# SmartSocket_V1_0.net
KiCad netlist of a schematic drawn in Altium Designer
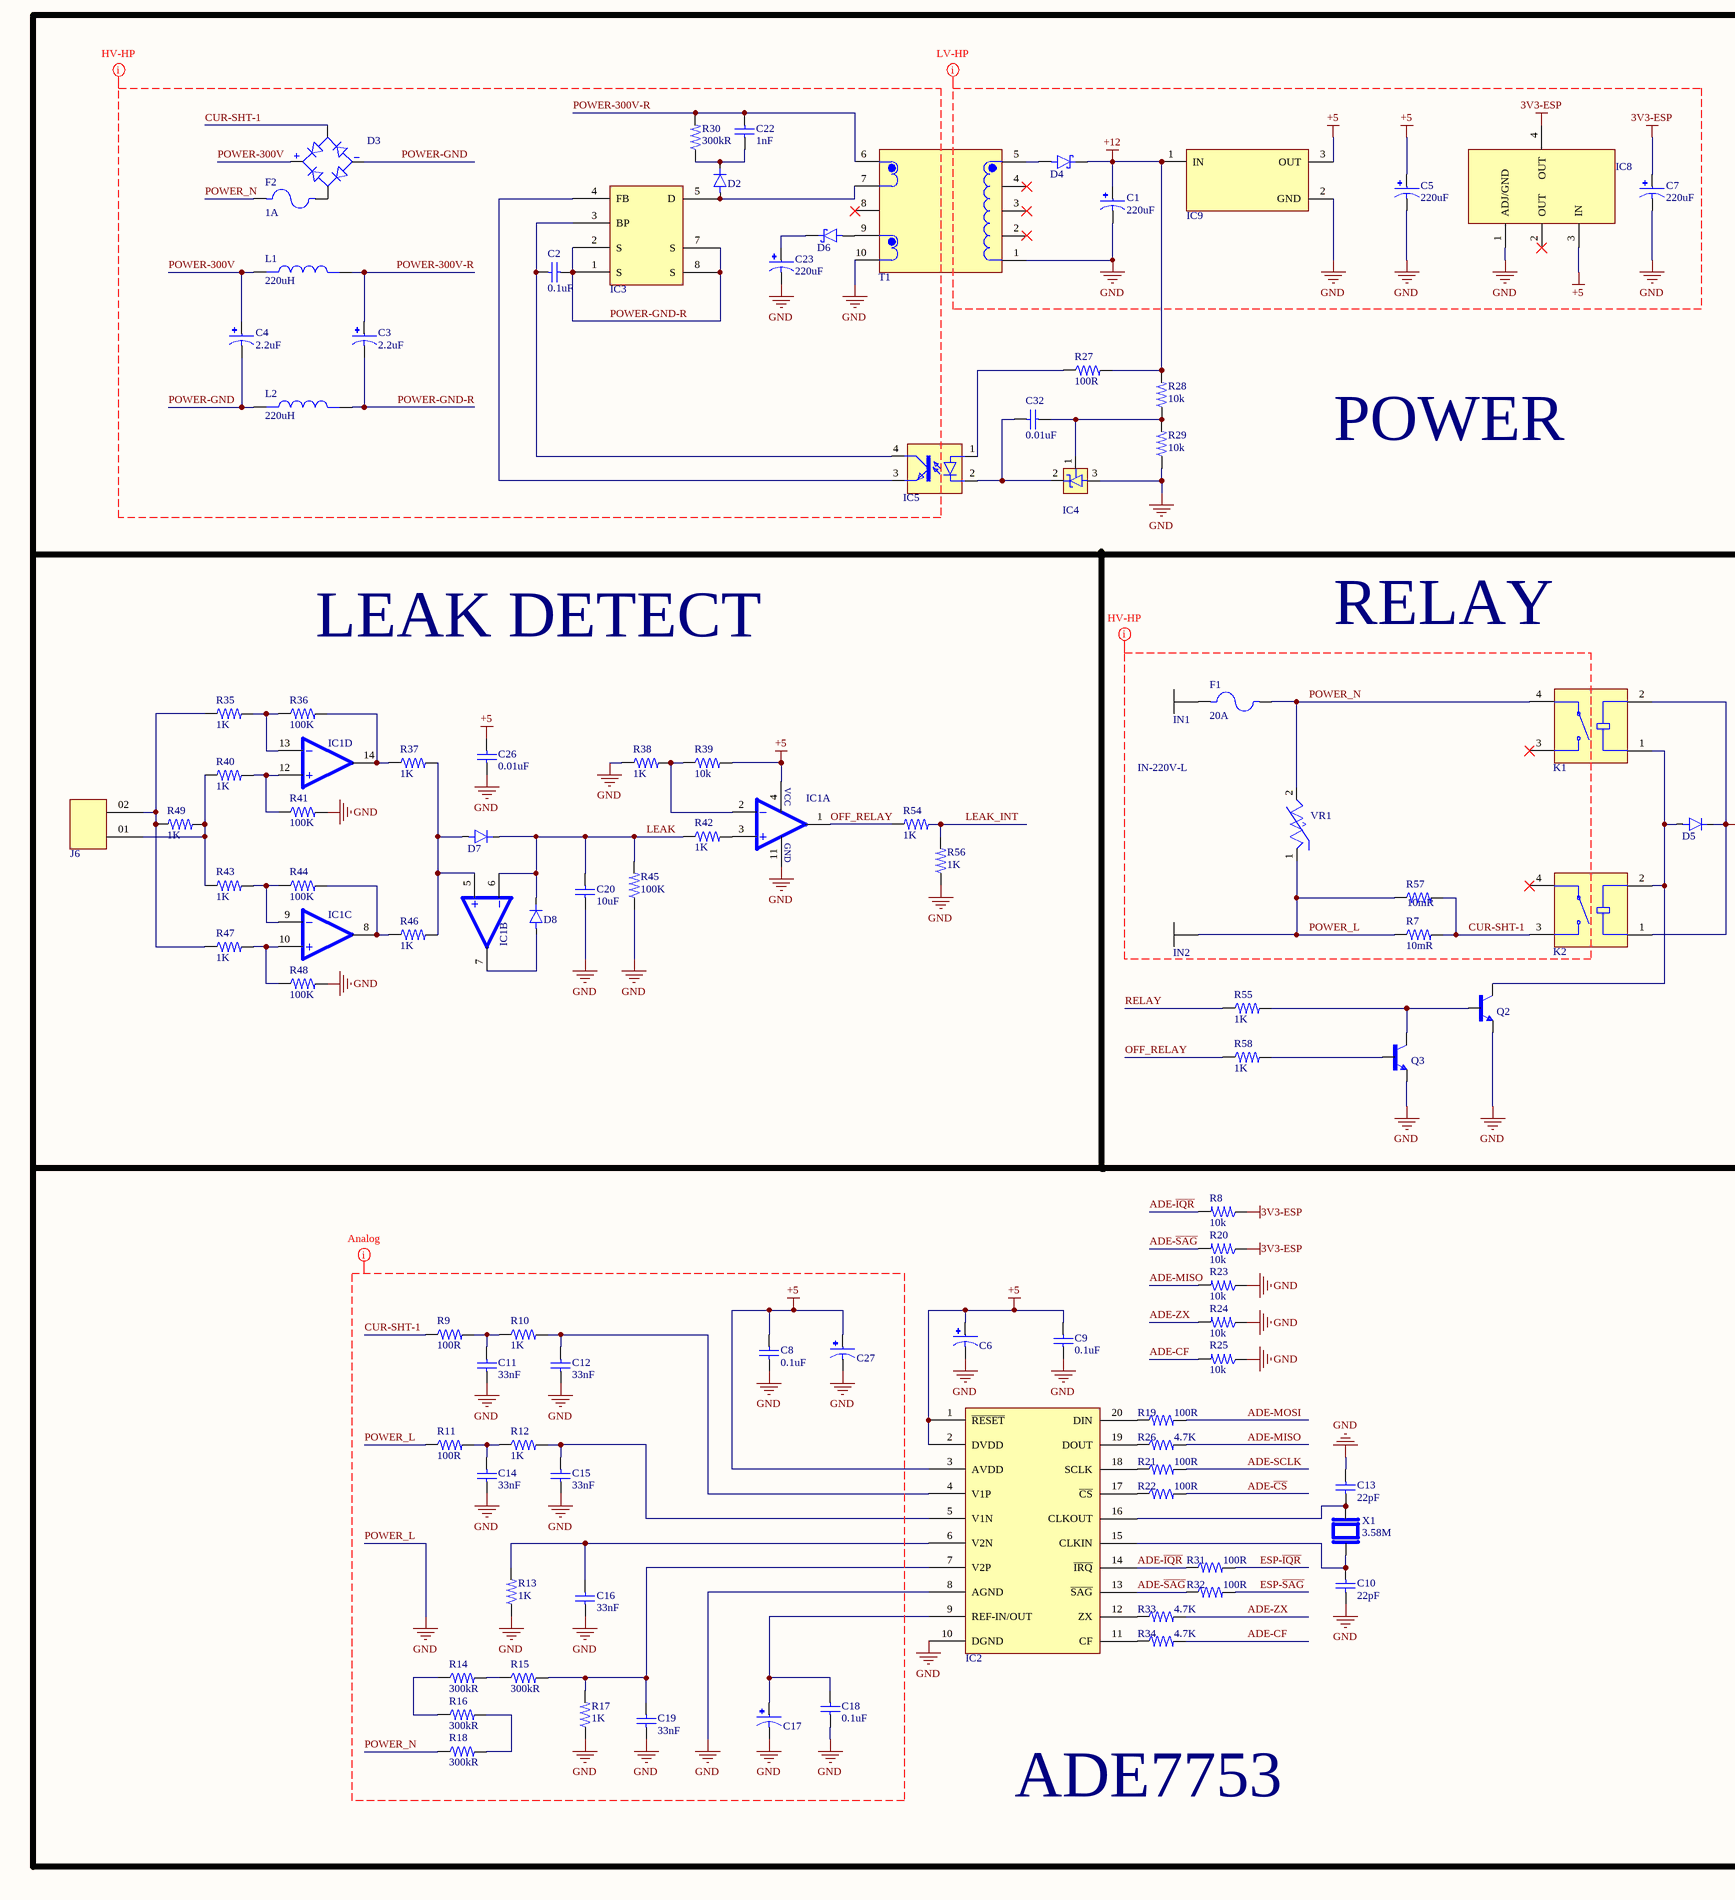
[diagram p0: SmartSocket V1.0.SchDoc, left]
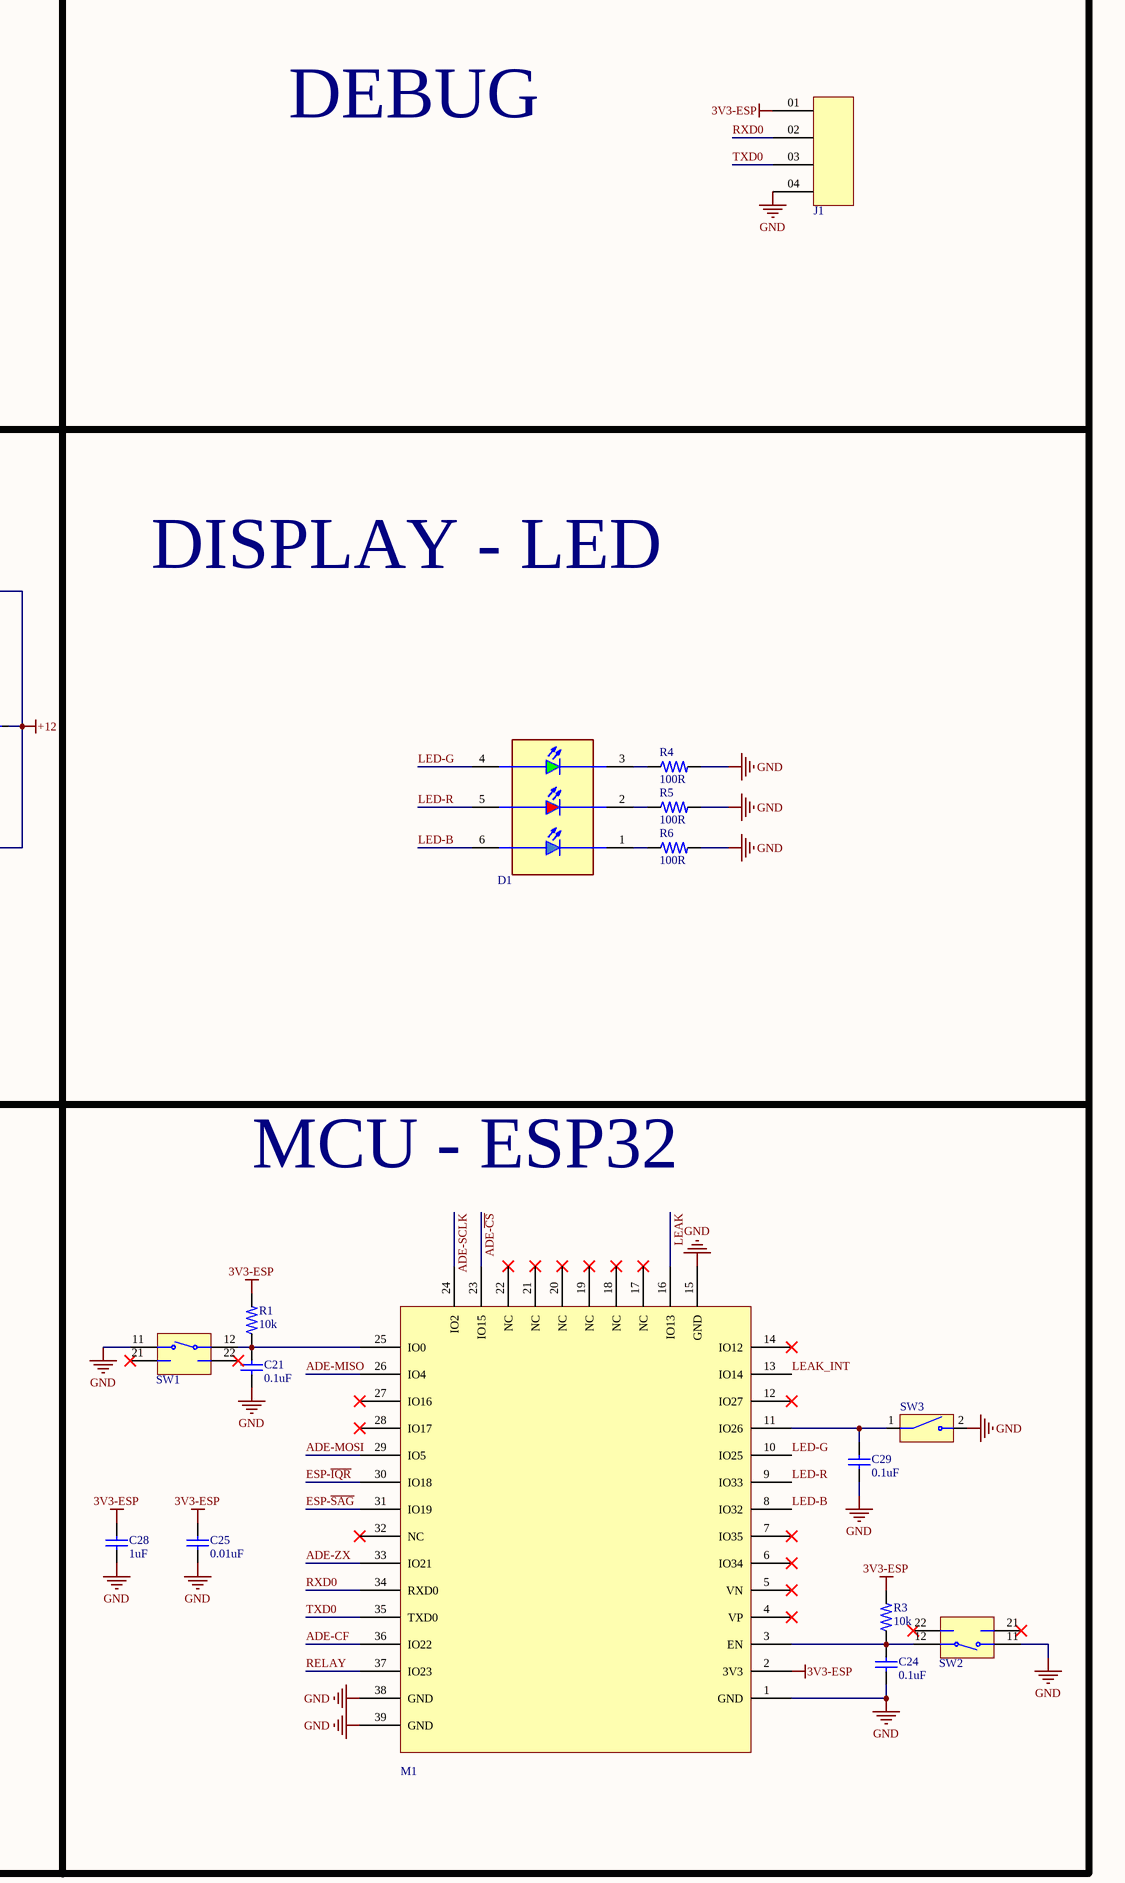
[diagram p1: SmartSocket V1.0.SchDoc, right]

(export (version "E")
  (design (tool "Eeschema 10.0.6"))
  (components
    (comp (ref "C1")
      (value "220uF")
      (footprint "SMD-DxLxW-6.3x6.6x6.6-PEC")
      (description "Cap Aluminum Polymer 220uF 16VDC 20% (6.3 X 5.9mm) SMD 0.022 Ohm 1040mA 1000h 125C T/R")
      (fields
        (field (name "MANUFACTURER") "Panasonic")
        (field (name "MANUFACTURER PART NUMBER") "16SVPK220M")
        (field (name "DESIGNER") "TVBac")
      )
      (libsource (lib "Capacitors") (part "CAP; 220uF; 16V; SMD; 16SVPK220M"))
    )
    (comp (ref "C2")
      (value "0.1uF")
      (footprint "SMD-CAP-0603-YAGEO")
      (description "Multilayer Ceramic Capacitor, 0.1 uF, 50 V, ï¿½ 5%, X7R, 0603 [1608 Metric]")
      (fields
        (field (name "MANUFACTURER") "Yageo")
        (field (name "MANUFACTURER PART NUMBER") "CC0603JRX7R9BB104")
        (field (name "DESIGNER") "TVBac")
      )
      (libsource (lib "Capacitors") (part "CAP; 0.1uF; 50V; 0603; SMD; CC0603JRX7R9BB104"))
    )
    (comp (ref "C3")
      (value "2.2uF")
      (footprint "TH-CAP-HxD-12.5x8.0-PEC")
      (description "Cap Aluminum Lytic 2.2uF 400V 20% (8 X 11.5mm) Radial 3.5mm 50mA 2000h 85C Automotive Bulk")
      (fields
        (field (name "MANUFACTURER") "Panasonic")
        (field (name "MANUFACTURER PART NUMBER") "ECA-2GM2R2")
        (field (name "DESIGNER") "TVBac")
      )
      (libsource (lib "Capacitors") (part "CAP; TH; 2.2uF; 400V; ECA-2GM2R2"))
    )
    (comp (ref "C4")
      (value "2.2uF")
      (footprint "TH-CAP-HxD-12.5x8.0-PEC")
      (description "Cap Aluminum Lytic 2.2uF 400V 20% (8 X 11.5mm) Radial 3.5mm 50mA 2000h 85C Automotive Bulk")
      (fields
        (field (name "MANUFACTURER") "Panasonic")
        (field (name "MANUFACTURER PART NUMBER") "ECA-2GM2R2")
        (field (name "DESIGNER") "TVBac")
      )
      (libsource (lib "Capacitors") (part "CAP; TH; 2.2uF; 400V; ECA-2GM2R2"))
    )
    (comp (ref "C5")
      (value "220uF")
      (footprint "SMD-DxLxW-6.3x6.6x6.6-PEC")
      (description "Cap Aluminum Polymer 220uF 16VDC 20% (6.3 X 5.9mm) SMD 0.022 Ohm 1040mA 1000h 125C T/R")
      (fields
        (field (name "MANUFACTURER") "Panasonic")
        (field (name "MANUFACTURER PART NUMBER") "16SVPK220M")
        (field (name "DESIGNER") "TVBac")
      )
      (libsource (lib "Capacitors") (part "CAP; 220uF; 16V; SMD; 16SVPK220M"))
    )
    (comp (ref "C6")
      (value "10 µF Molded Tantalum Capacitors 10 V 1206 (3216 Metric) 3.8Ohm")
      (footprint "SMD-CAP-TAN-1206-KEMET")
      (description "Capacitor, Tantalum, Solid, Polarized, 10 V, 10 Uf, Surface Mount, 1206, Lead Free")
      (fields
        (field (name "MANUFACTURER") "KEMET")
        (field (name "MANUFACTURER PART NUMBER") "T491A106M010AT")
        (field (name "DESIGNER") "TVBac")
      )
      (libsource (lib "Capacitors") (part "CAP; CAP_TAN; 10uF; 10V; T491A106M010AT"))
    )
    (comp (ref "C7")
      (value "220uF")
      (footprint "SMD-DxLxW-6.3x6.6x6.6-PEC")
      (description "Cap Aluminum Polymer 220uF 10VDC 20%( 6.3 X 5.9mm) SMD 0.02 Ohm 2700mA 2000h 105C T/R")
      (fields
        (field (name "MANUFACTURER") "Panasonic")
        (field (name "MANUFACTURER PART NUMBER") "10SVPE220M")
        (field (name "DESIGNER") "TVBac")
      )
      (libsource (lib "Capacitors") (part "CAP; 220uF; 10V; SMD; 10SVPE220M"))
    )
    (comp (ref "C8")
      (value "0.1uF")
      (footprint "SMD-CAP-0603-YAGEO")
      (description "0603 0.1 uF 16 V ±10 % Tolerance X7R SMT Multilayer Ceramic Capacitor")
      (fields
        (field (name "MANUFACTURER") "Yageo")
        (field (name "MANUFACTURER PART NUMBER") "CC0603KRX7R7BB104")
        (field (name "DESIGNER") "TVBac")
      )
      (libsource (lib "Capacitors") (part "CAP; 0.1uF; 16V; 0603; SMD; CC0603KRX7R7BB104"))
    )
    (comp (ref "C9")
      (value "0.1uF")
      (footprint "SMD-CAP-0603-YAGEO")
      (description "0603 0.1 uF 16 V ±10 % Tolerance X7R SMT Multilayer Ceramic Capacitor")
      (fields
        (field (name "MANUFACTURER") "Yageo")
        (field (name "MANUFACTURER PART NUMBER") "CC0603KRX7R7BB104")
        (field (name "DESIGNER") "TVBac")
      )
      (libsource (lib "Capacitors") (part "CAP; 0.1uF; 16V; 0603; SMD; CC0603KRX7R7BB104"))
    )
    (comp (ref "C10")
      (value "22pF")
      (footprint "SMD-CAP-0603-YAGEO")
      (description "Multilayer Ceramic Capacitor, 22 pF, 50 V, ï¿½ 1%, C0G (NP0), 0603 [1608 Metric]")
      (fields
        (field (name "MANUFACTURER") "Yageo")
        (field (name "MANUFACTURER PART NUMBER") "CC0603FRNPO9BN220")
        (field (name "DESIGNER") "TVBac")
      )
      (libsource (lib "Capacitors") (part "CAP; 22pF; 50V; SMD; CC0603FRNPO9BN220"))
    )
    (comp (ref "C11")
      (value "33nF")
      (footprint "SMD-CAP-0603-KEMET")
      (description "Multilayer Ceramic Capacitors MLCC - SMD/SMT 16V 0.033uF X7R 0603 5%")
      (fields
        (field (name "MANUFACTURER") "KEMET")
        (field (name "MANUFACTURER PART NUMBER") "C0603C333J4REC7411")
        (field (name "DESIGNER") "TVBac")
      )
      (libsource (lib "Capacitors") (part "CAP; 0.033uF; 33nF; 0603; 16V; C0603C333J4REC7411"))
    )
    (comp (ref "C12")
      (value "33nF")
      (footprint "SMD-CAP-0603-KEMET")
      (description "Multilayer Ceramic Capacitors MLCC - SMD/SMT 16V 0.033uF X7R 0603 5%")
      (fields
        (field (name "MANUFACTURER") "KEMET")
        (field (name "MANUFACTURER PART NUMBER") "C0603C333J4REC7411")
        (field (name "DESIGNER") "TVBac")
      )
      (libsource (lib "Capacitors") (part "CAP; 0.033uF; 33nF; 0603; 16V; C0603C333J4REC7411"))
    )
    (comp (ref "C13")
      (value "22pF")
      (footprint "SMD-CAP-0603-YAGEO")
      (description "Multilayer Ceramic Capacitor, 22 pF, 50 V, ï¿½ 1%, C0G (NP0), 0603 [1608 Metric]")
      (fields
        (field (name "MANUFACTURER") "Yageo")
        (field (name "MANUFACTURER PART NUMBER") "CC0603FRNPO9BN220")
        (field (name "DESIGNER") "TVBac")
      )
      (libsource (lib "Capacitors") (part "CAP; 22pF; 50V; SMD; CC0603FRNPO9BN220"))
    )
    (comp (ref "C14")
      (value "33nF")
      (footprint "SMD-CAP-0603-KEMET")
      (description "Multilayer Ceramic Capacitors MLCC - SMD/SMT 16V 0.033uF X7R 0603 5%")
      (fields
        (field (name "MANUFACTURER") "KEMET")
        (field (name "MANUFACTURER PART NUMBER") "C0603C333J4REC7411")
        (field (name "DESIGNER") "TVBac")
      )
      (libsource (lib "Capacitors") (part "CAP; 0.033uF; 33nF; 0603; 16V; C0603C333J4REC7411"))
    )
    (comp (ref "C15")
      (value "33nF")
      (footprint "SMD-CAP-0603-KEMET")
      (description "Multilayer Ceramic Capacitors MLCC - SMD/SMT 16V 0.033uF X7R 0603 5%")
      (fields
        (field (name "MANUFACTURER") "KEMET")
        (field (name "MANUFACTURER PART NUMBER") "C0603C333J4REC7411")
        (field (name "DESIGNER") "TVBac")
      )
      (libsource (lib "Capacitors") (part "CAP; 0.033uF; 33nF; 0603; 16V; C0603C333J4REC7411"))
    )
    (comp (ref "C16")
      (value "33nF")
      (footprint "SMD-CAP-0603-KEMET")
      (description "Multilayer Ceramic Capacitors MLCC - SMD/SMT 16V 0.033uF X7R 0603 5%")
      (fields
        (field (name "MANUFACTURER") "KEMET")
        (field (name "MANUFACTURER PART NUMBER") "C0603C333J4REC7411")
        (field (name "DESIGNER") "TVBac")
      )
      (libsource (lib "Capacitors") (part "CAP; 0.033uF; 33nF; 0603; 16V; C0603C333J4REC7411"))
    )
    (comp (ref "C17")
      (value "10 µF Molded Tantalum Capacitors 10 V 1206 (3216 Metric) 3.8Ohm")
      (footprint "SMD-CAP-TAN-1206-KEMET")
      (description "Capacitor, Tantalum, Solid, Polarized, 10 V, 10 Uf, Surface Mount, 1206, Lead Free")
      (fields
        (field (name "MANUFACTURER") "KEMET")
        (field (name "MANUFACTURER PART NUMBER") "T491A106M010AT")
        (field (name "DESIGNER") "TVBac")
      )
      (libsource (lib "Capacitors") (part "CAP; CAP_TAN; 10uF; 10V; T491A106M010AT"))
    )
    (comp (ref "C18")
      (value "0.1uF")
      (footprint "SMD-CAP-0603-YAGEO")
      (description "0603 0.1 uF 16 V ±10 % Tolerance X7R SMT Multilayer Ceramic Capacitor")
      (fields
        (field (name "MANUFACTURER") "Yageo")
        (field (name "MANUFACTURER PART NUMBER") "CC0603KRX7R7BB104")
        (field (name "DESIGNER") "TVBac")
      )
      (libsource (lib "Capacitors") (part "CAP; 0.1uF; 16V; 0603; SMD; CC0603KRX7R7BB104"))
    )
    (comp (ref "C19")
      (value "33nF")
      (footprint "SMD-CAP-0603-KEMET")
      (description "Multilayer Ceramic Capacitors MLCC - SMD/SMT 16V 0.033uF X7R 0603 5%")
      (fields
        (field (name "MANUFACTURER") "KEMET")
        (field (name "MANUFACTURER PART NUMBER") "C0603C333J4REC7411")
        (field (name "DESIGNER") "TVBac")
      )
      (libsource (lib "Capacitors") (part "CAP; 0.033uF; 33nF; 0603; 16V; C0603C333J4REC7411"))
    )
    (comp (ref "C20")
      (value "10uF")
      (footprint "SMD-CAP-0805-KEMET")
      (description "Multilayer Ceramic Capacitor, 10 uF, 6.3 V, ï¿½ 10%, X5R, 0805 [2012 Metric]")
      (fields
        (field (name "MANUFACTURER") "KEMET")
        (field (name "MANUFACTURER PART NUMBER") "C0805C106K9PACTU")
        (field (name "DESIGNER") "TVBac")
      )
      (libsource (lib "Capacitors") (part "CAP; 10uF; 10V; 0805; C0805C106K9PACTU"))
    )
    (comp (ref "C21")
      (value "0.1uF")
      (footprint "SMD-CAP-0603-YAGEO")
      (description "Multilayer Ceramic Capacitor, 0.1 uF, 25 V, ï¿½ 5%, X7R, 0603 [1608 Metric]")
      (fields
        (field (name "MANUFACTURER") "Yageo")
        (field (name "MANUFACTURER PART NUMBER") "CC0603JRX7R8BB104")
        (field (name "DESIGNER") "TVBac")
      )
      (libsource (lib "Capacitors") (part "CAP; 0.1uF; 25V; 0603; SMD; CC0603JRX7R8BB104"))
    )
    (comp (ref "C22")
      (value "1nF")
      (footprint "TH-CAP-HxLxW-5.5x4.0x2.5-TDKC")
      (description "Capacitor Ceramic 0.001uF 50V C0G 5% 5mm T/R")
      (fields
        (field (name "MANUFACTURER") "TDK")
        (field (name "MANUFACTURER PART NUMBER") "FA28NP01H102JNU06")
        (field (name "DESIGNER") "TVBac")
      )
      (libsource (lib "Capacitors") (part "CAP; TH; 0.001uF; 50V; FA28NP01H102JNU06"))
    )
    (comp (ref "C23")
      (value "220uF")
      (footprint "SMD-DxLxW-8.0x8.3x8.3-PEC")
      (description "Cap Aluminum 220uF 25V 20% (8 X 10.2mm) SMD 0.027 Ohm 2300mA 5000h 105 C Embossed T/R")
      (fields
        (field (name "MANUFACTURER") "Panasonic")
        (field (name "MANUFACTURER PART NUMBER") "EEH-ZA1E221P")
        (field (name "DESIGNER") "TVBac")
      )
      (libsource (lib "Capacitors") (part "CAP; 220uF; 25V; SMD; EEH-ZA1E221P"))
    )
    (comp (ref "C24")
      (value "0.1uF")
      (footprint "SMD-CAP-0603-YAGEO")
      (description "Multilayer Ceramic Capacitor, 0.1 uF, 25 V, ï¿½ 5%, X7R, 0603 [1608 Metric]")
      (fields
        (field (name "MANUFACTURER") "Yageo")
        (field (name "MANUFACTURER PART NUMBER") "CC0603JRX7R8BB104")
        (field (name "DESIGNER") "TVBac")
      )
      (libsource (lib "Capacitors") (part "CAP; 0.1uF; 25V; 0603; SMD; CC0603JRX7R8BB104"))
    )
    (comp (ref "C25")
      (value "0.01uF")
      (footprint "SMD-CAP-0603-YAGEO")
      (description "Multilayer Ceramic Capacitor, 0.1 uF, 10 V, ± 10%, X7R, 0603 [1608 Metric]")
      (fields
        (field (name "MANUFACTURER") "Yageo")
        (field (name "MANUFACTURER PART NUMBER") "CC0603KRX7R6BB104")
        (field (name "DESIGNER") "TVBac")
      )
      (libsource (lib "Capacitors") (part "CAP; 0.1uF; 10V; 0603; SMD; CC0603KRX7R6BB104"))
    )
    (comp (ref "C26")
      (value "0.01uF")
      (footprint "SMD-CAP-0603-YAGEO")
      (description "Multilayer Ceramic Capacitor, 0.1 uF, 10 V, ± 10%, X7R, 0603 [1608 Metric]")
      (fields
        (field (name "MANUFACTURER") "Yageo")
        (field (name "MANUFACTURER PART NUMBER") "CC0603KRX7R6BB104")
        (field (name "DESIGNER") "TVBac")
      )
      (libsource (lib "Capacitors") (part "CAP; 0.1uF; 10V; 0603; SMD; CC0603KRX7R6BB104"))
    )
    (comp (ref "C27")
      (value "10 µF Molded Tantalum Capacitors 10 V 1206 (3216 Metric) 3.8Ohm")
      (footprint "SMD-CAP-TAN-1206-KEMET")
      (description "Capacitor, Tantalum, Solid, Polarized, 10 V, 10 Uf, Surface Mount, 1206, Lead Free")
      (fields
        (field (name "MANUFACTURER") "KEMET")
        (field (name "MANUFACTURER PART NUMBER") "T491A106M010AT")
        (field (name "DESIGNER") "TVBac")
      )
      (libsource (lib "Capacitors") (part "CAP; CAP_TAN; 10uF; 10V; T491A106M010AT"))
    )
    (comp (ref "C28")
      (value "1uF")
      (footprint "SMD-CAP-0603-YAGEO")
      (description "0603 1 uF 16 V ±10 % Tolerance X7R SMT Multilayer Ceramic Capacitor")
      (fields
        (field (name "MANUFACTURER") "Yageo")
        (field (name "MANUFACTURER PART NUMBER") "CC0603KRX7R7BB105")
        (field (name "DESIGNER") "TVBac")
      )
      (libsource (lib "Capacitors") (part "CAP; 1uF; 16V; 0603; SMD; CC0603KRX7R7BB105"))
    )
    (comp (ref "C29")
      (value "0.1uF")
      (footprint "SMD-CAP-0603-YAGEO")
      (description "Multilayer Ceramic Capacitor, 0.1 uF, 25 V, ï¿½ 5%, X7R, 0603 [1608 Metric]")
      (fields
        (field (name "MANUFACTURER") "Yageo")
        (field (name "MANUFACTURER PART NUMBER") "CC0603JRX7R8BB104")
        (field (name "DESIGNER") "TVBac")
      )
      (libsource (lib "Capacitors") (part "CAP; 0.1uF; 25V; 0603; SMD; CC0603JRX7R8BB104"))
    )
    (comp (ref "C32")
      (value "0.01uF")
      (footprint "SMD-CAP-0603-YAGEO")
      (description "Surface Mount Ceramic Multilayer Capacitor 0.01uF 5% X7R 25V 0603 Paper T/R")
      (fields
        (field (name "MANUFACTURER") "Yageo")
        (field (name "MANUFACTURER PART NUMBER") "CC0603JRX7R8BB103")
        (field (name "DESIGNER") "TVBac")
      )
      (libsource (lib "Capacitors") (part "CAP; 0.01uF; 25V; 0603; SMD; CC0603JRX7R8BB103"))
    )
    (comp (ref "D1")
      (value "Red, Green, Blue (RGB) 625nm Red, 525nm Green, 568nm Blue LED Indication - Discrete 2V Red, 3.2V Green, 3.3V Blue 6-SMD, J-Lead")
      (footprint "SMD-HxLxW-1.6x5.0x5.0-ABOC")
      (description "5050 PLCC6 Rgb")
      (fields
        (field (name "MANUFACTURER") "American Bright")
        (field (name "MANUFACTURER PART NUMBER") "BL-HBXJXGX32L")
        (field (name "DESIGNER") "TVBac")
      )
      (libsource (lib "Smartsocket") (part "LED; RGB; SMD; BL-HBXJXGX32L"))
    )
    (comp (ref "D2")
      (value "Diode 1000 V 1A Surface Mount SOD-123FL")
      (footprint "SOD-123FL-SMCDS")
      (description "Diode Gen Purp 1KV 1A SOD123FL")
      (fields
        (field (name "MANUFACTURER") "Sangdest Microelectronics")
        (field (name "MANUFACTURER PART NUMBER") "1N4007FL")
        (field (name "DESIGNER") "TVBac")
      )
      (libsource (lib "Diode") (part "DIODE; SMD; 1N4007FLN4007;"))
    )
    (comp (ref "D3")
      (value "Bridge Rectifier Single Phase Standard 1 kV Surface Mount ABS")
      (footprint "DIODE-SMD-4-TSC")
      (description "Bridge Rectifiers 1A, 1000V, Standard Bridge Rectifier")
      (fields
        (field (name "MANUFACTURER") "Taiwan Semiconductor")
        (field (name "MANUFACTURER PART NUMBER") "ABS10H")
        (field (name "DESIGNER") "TVBac")
      )
      (libsource (lib "Diode") (part "DIODE; SMD; ABS10H"))
    )
    (comp (ref "D4")
      (value "Diode 40 V 3A Surface Mount DO-214AC (SMA)")
      (footprint "SMD-DO-214AC-214-CT")
      (description "Diode Schottky Si 40V 3A 2-Pin SMA T/R")
      (fields
        (field (name "MANUFACTURER") "Comchip")
        (field (name "MANUFACTURER PART NUMBER") "SS34-HF")
        (field (name "DESIGNER") "TVBac")
      )
      (libsource (lib "Smartsocket") (part "DIODE; SMD; SCHOTTKY; SS34-HF"))
    )
    (comp (ref "D5")
      (value "Diode 1000 V 1A Surface Mount SOD-123FL")
      (footprint "SOD-123FL-SMCDS")
      (description "Diode Gen Purp 1KV 1A SOD123FL")
      (fields
        (field (name "MANUFACTURER") "Sangdest Microelectronics")
        (field (name "MANUFACTURER PART NUMBER") "1N4007FL")
        (field (name "DESIGNER") "TVBac")
      )
      (libsource (lib "Diode") (part "DIODE; SMD; 1N4007FLN4007;"))
    )
    (comp (ref "D6")
      (value "Diode 40 V 3A Surface Mount DO-214AC (SMA)")
      (footprint "SMD-DO-214AC-214-CT")
      (description "Diode Schottky Si 40V 3A 2-Pin SMA T/R")
      (fields
        (field (name "MANUFACTURER") "Comchip")
        (field (name "MANUFACTURER PART NUMBER") "SS34-HF")
        (field (name "DESIGNER") "TVBac")
      )
      (libsource (lib "Smartsocket") (part "DIODE; SMD; SCHOTTKY; SS34-HF"))
    )
    (comp (ref "D7")
      (value "Diode 1000 V 1A Surface Mount SOD-123FL")
      (footprint "SOD-123FL-SMCDS")
      (description "Diode Gen Purp 1KV 1A SOD123FL")
      (fields
        (field (name "MANUFACTURER") "Sangdest Microelectronics")
        (field (name "MANUFACTURER PART NUMBER") "1N4007FL")
        (field (name "DESIGNER") "TVBac")
      )
      (libsource (lib "Diode") (part "DIODE; SMD; 1N4007FLN4007;"))
    )
    (comp (ref "D8")
      (value "Diode 1000 V 1A Surface Mount SOD-123FL")
      (footprint "SOD-123FL-SMCDS")
      (description "Diode Gen Purp 1KV 1A SOD123FL")
      (fields
        (field (name "MANUFACTURER") "Sangdest Microelectronics")
        (field (name "MANUFACTURER PART NUMBER") "1N4007FL")
        (field (name "DESIGNER") "TVBac")
      )
      (libsource (lib "Diode") (part "DIODE; SMD; 1N4007FLN4007;"))
    )
    (comp (ref "F1")
      (value "20A")
      (footprint "FUSE-5mmx20mm-AXIAL-BFI")
      (description "Fuse 20A 600VAC 500VDC Time Delay 2-Pin Through Hole")
      (fields
        (field (name "MANUFACTURER") "Bel")
        (field (name "MANUFACTURER PART NUMBER") "0ADKP9200-RE")
        (field (name "DESIGNER") "TVBac")
      )
      (libsource (lib "Socket") (part "FUSE; 20A; 0ADKP9200-RE"))
    )
    (comp (ref "F2")
      (value "1A")
      (footprint "FUSE-HxLxW-8.0x8.5x4.0-LI")
      (description "Fuse Subminiature Slow Blow Acting 1A 300V Radial 8.5 X 4 X 8mm Ammo Pack")
      (fields
        (field (name "MANUFACTURER") "Littelfuse Wickmann")
        (field (name "MANUFACTURER PART NUMBER") "36911000000")
        (field (name "DESIGNER") "TVBac")
      )
      (libsource (lib "Smartsocket") (part "FUSE; 1A; 36911000000"))
    )
    (comp (ref "IC1")
      (value "General Purpose Amplifier 4 Circuit 14-SOIC")
      (footprint "SOIC-14")
      (description "Quad 30-V 1.2-MHz operational amplifier 14-SOIC 0 to 70")
      (fields
        (field (name "MANUFACTURER") "Texas Instruments")
        (field (name "MANUFACTURER PART NUMBER") "LM324DR")
        (field (name "DESIGNER") "TVBac")
      )
      (libsource (lib "IC") (part "OPAM; SMD; LM324DR"))
    )
    (comp (ref "IC2")
      (value "Single Phase Meter IC 20-SSOP")
      (footprint "SSOP-20-ADI")
      (description "Single Phase Multifunction Metering IC 20-Pin SSOP Tube")
      (fields
        (field (name "MANUFACTURER") "Analog Devices")
        (field (name "MANUFACTURER PART NUMBER") "ADE7753ARSZ")
        (field (name "DESIGNER") "TVBac")
      )
      (libsource (lib "IC") (part "ADE7753ARSZ"))
    )
    (comp (ref "IC3")
      (value "Converter Offline Flyback Topology 132kHz SMD-8B")
      (footprint "SMD-8B-PI")
      (description "AC to DC Switching Converter Off-Line Switcher 140kHz 7-Pin SMD-B / IC OFFLINE SWIT HV 8SMD")
      (fields
        (field (name "MANUFACTURER") "Power Integrations")
        (field (name "MANUFACTURER PART NUMBER") "LNK364GN-TL")
        (field (name "DESIGNER") "TVBac")
      )
      (libsource (lib "Smartsocket") (part "LNK364GN-TL"))
    )
    (comp (ref "IC4")
      (value "Shunt Voltage Reference IC Adjustable 2.495V 36 VV ±1% 100 mA SOT-23-3")
      (footprint "SOT-23-3-DS")
      (description "V-Ref Adjustable 2.495V to 36V 100mA Automotive 3-Pin SOT-23 T/R")
      (fields
        (field (name "MANUFACTURER") "Texas Instruments")
        (field (name "MANUFACTURER PART NUMBER") "TL431AIDBZR")
        (field (name "DESIGNER") "TVBac")
      )
      (libsource (lib "IC") (part "TL431AIDBZR; MIRROID;"))
    )
    (comp (ref "IC5")
      (value "Optoisolator Transistor Output 3750Vrms 1 Channel 4-SOP (2.54mm)")
      (footprint "SOP-4")
      (description "Transistor Output Optocoupler, 1-Element, 3750V Isolation")
      (fields (field (name "MANUFACTURER") "Everlight") (field (name "MANUFACTURER PART NUMBER") "EL357N-G"))
      (libsource (lib "IC") (part "ISO; 1CH; EL357N-G"))
    )
    (comp (ref "IC8")
      (value "Linear Voltage Regulator IC Positive Fixed 1 Output 1A SOT-223-3")
      (footprint "IC:SOT-223-3-DI")
      (description "Linear Voltage Regulator IC 1 Output 1A SOT-223")
      (fields
        (field (name "MF") "Diodes Inc.")
        (field (name "MP") "AZ1117EH-3.3TRG1")
        (field (name "DESIGNER") "TVBac")
      )
      (libsource (lib "IC") (part "LDO; 3V3; 1A; SMD; AZ1117EH-3.3TRG1"))
    )
    (comp (ref "IC9")
      (value "Linear Voltage Regulator IC Positive Fixed 1 Output 1A TO-252")
      (footprint "TO252-3-RS")
      (description "Linear Voltage Regulator, Fixed, Positive Output, 7.5 V to 25 V, 5V, 1A, 3 Pins, TO-252 (DPAK)")
      (fields
        (field (name "MANUFACTURER") "Rohm")
        (field (name "MANUFACTURER PART NUMBER") "BA17805FP-E2")
        (field (name "DESIGNER") "TVBac")
      )
      (libsource (lib "IC") (part "LDO; 5V; 1A; BA17805FP-E2"))
    )
    (comp (ref "IN1")
      (value "INPUT")
      (footprint "INPUT-2.0x3.5")
      (fields (field (name "DESIGNER") "TVBac"))
      (libsource (lib "Socket") (part "INPUT-2.0x3.5"))
    )
    (comp (ref "IN2")
      (value "INPUT")
      (footprint "INPUT-2.0x3.5")
      (fields (field (name "DESIGNER") "TVBac"))
      (libsource (lib "Socket") (part "INPUT-2.0x3.5"))
    )
    (comp (ref "J1")
      (value "Connector Header Through Hole 4 position 0.100\" (2.54mm)")
      (footprint "HEADER-2.54-4")
      (description "Conn Unshrouded Header HDR 4 POS 2.54mm Solder ST Thru-Hole Automotive Bulk")
      (fields
        (field (name "MANUFACTURER") "Samtec")
        (field (name "MANUFACTURER PART NUMBER") "TSW-104-14-L-S")
        (field (name "DESIGNER") "TVBac")
      )
      (libsource (lib "Socket") (part "HEADER; 4PIN; 2.54; VER; TSW-104-14-L-S"))
    )
    (comp (ref "J6")
      (value "Connector Header Through Hole 2 position")
      (footprint "HEADER-2.54-2")
      (description "Headers & Wire Housings Classic PCB Header Strips, 0.100 pitch")
      (fields
        (field (name "MANUFACTURER") "Samtec")
        (field (name "MANUFACTURER PART NUMBER") "TSW-101-15-T-D")
        (field (name "DESIGNER") "TVBac")
      )
      (libsource (lib "Socket") (part "HEADER; 2PIN; 2.54; VER; TSW-101-15-T-D"))
    )
    (comp (ref "K1")
      (value "General Purpose Relay SPST-NO (1 Form A) 12VDC Coil Through Hole")
      (footprint "RELAY-HxLxW-23.5x30.5x15.7-OEIEMCD-D")
      (description "Electromechanical Relay 12VDC 160Ohm 20A SPST-NO (30.5x16x33.5)mm THT Power Relay")
      (fields
        (field (name "MANUFACTURER") "Omron")
        (field (name "MANUFACTURER PART NUMBER") "G4A-1A-E-DC12")
        (field (name "DESIGNER") "TVBac")
      )
      (libsource (lib "Relay") (part "RELAY; SINGLE; 20A; 12VDC; G4A-1A-E-DC12"))
    )
    (comp (ref "K2")
      (value "General Purpose Relay SPST-NO (1 Form A) 12VDC Coil Through Hole")
      (footprint "RELAY-HxLxW-23.5x30.5x15.7-OEIEMCD-D")
      (description "Electromechanical Relay 12VDC 160Ohm 20A SPST-NO (30.5x16x33.5)mm THT Power Relay")
      (fields
        (field (name "MANUFACTURER") "Omron")
        (field (name "MANUFACTURER PART NUMBER") "G4A-1A-E-DC12")
        (field (name "DESIGNER") "TVBac")
      )
      (libsource (lib "Relay") (part "RELAY; SINGLE; 20A; 12VDC; G4A-1A-E-DC12"))
    )
    (comp (ref "L1")
      (value "220uH")
      (footprint "SMD-HxLxW-1.8x4.0x4.0-ALLC")
      (description "Power Inductor (SMD), 220 uH, ± 20%, 250 mA, Shielded, 330 mA, 4mm x 4mm x 1.8mm")
      (fields
        (field (name "MANUFACTURER") "Abracon")
        (field (name "MANUFACTURER PART NUMBER") "ASPI-0418FS-221M-T3")
        (field (name "DESIGNER") "TVBac")
      )
      (libsource (lib "Inductors") (part "IND; 220uH; 250mA; ASPI-0418FS-221M-T3"))
    )
    (comp (ref "L2")
      (value "220uH")
      (footprint "SMD-HxLxW-1.8x4.0x4.0-ALLC")
      (description "Power Inductor (SMD), 220 uH, ± 20%, 250 mA, Shielded, 330 mA, 4mm x 4mm x 1.8mm")
      (fields
        (field (name "MANUFACTURER") "Abracon")
        (field (name "MANUFACTURER PART NUMBER") "ASPI-0418FS-221M-T3")
        (field (name "DESIGNER") "TVBac")
      )
      (libsource (lib "Inductors") (part "IND; 220uH; 250mA; ASPI-0418FS-221M-T3"))
    )
    (comp (ref "M1")
      (value "Bluetooth, WiFi 802.11b/g/n, Bluetooth v4.2 +EDR, Class 1, 2 and 3 Transceiver Module 2.4GHz ~ 2.5GHz Integrated, Trace Surface Mount")
      (footprint "MODULE-ESP32-WROVER - WROOM")
      (description "Rf Txrx Module Bt Trace Ant SMD")
      (fields
        (field (name "MANUFACTURER") "Espressif Systems")
        (field (name "MANUFACTURER PART NUMBER") "ESP32-WROOM-32E-H4")
        (field (name "DESIGNER") "TVBac")
      )
      (libsource (lib "Modules") (part "ESP32-WROOM-WROVE-32E-H4; SMD;"))
    )
    (comp (ref "Q2")
      (value "Bipolar (BJT) Transistor NPN 45 V 500 mA 100MHz 300 mW Surface Mount SOT-23-3 (TO-236)")
      (footprint "SOT-23-3-ONSEMI")
      (description "Single Bipolar Transistor, NPN, 45 V, 500 mA, 225 mW, SOT-23 (TO-236), 3 Pins, Surface Mount")
      (fields
        (field (name "MANUFACTURER") "ON Semiconductor")
        (field (name "MANUFACTURER PART NUMBER") "BC817-25LT1G")
        (field (name "DESIGNER") "TVBac")
      )
      (libsource (lib "Transistors") (part "TRAN; NPN; 500mA;V;  BC817-25LT1G"))
    )
    (comp (ref "Q3")
      (value "Bipolar (BJT) Transistor NPN 45 V 500 mA 100MHz 300 mW Surface Mount SOT-23-3 (TO-236)")
      (footprint "SOT-23-3-ONSEMI")
      (description "Single Bipolar Transistor, NPN, 45 V, 500 mA, 225 mW, SOT-23 (TO-236), 3 Pins, Surface Mount")
      (fields
        (field (name "MANUFACTURER") "ON Semiconductor")
        (field (name "MANUFACTURER PART NUMBER") "BC817-25LT1G")
        (field (name "DESIGNER") "TVBac")
      )
      (libsource (lib "Transistors") (part "TRAN; NPN; 500mA;V;  BC817-25LT1G"))
    )
    (comp (ref "R1")
      (value "10k")
      (footprint "SMD-RES-0603-SEI")
      (description "SMD Chip Resistor, 10 kOhm, ± 1%, 250 mW, 0603 [1608 Metric], Thick Film, Anti-Surge")
      (fields
        (field (name "MANUFACTURER") "Rohm")
        (field (name "MANUFACTURER PART NUMBER") "ESR03EZPF1002")
        (field (name "DESIGNER") "TVBac")
      )
      (libsource (lib "Smartsocket") (part "RES; 10K; 0603; SMD; ESR03EZPF1002"))
    )
    (comp (ref "R3")
      (value "10k")
      (footprint "SMD-RES-0603-SEI")
      (description "SMD Chip Resistor, 10 kOhm, ± 1%, 250 mW, 0603 [1608 Metric], Thick Film, Anti-Surge")
      (fields
        (field (name "MANUFACTURER") "Rohm")
        (field (name "MANUFACTURER PART NUMBER") "ESR03EZPF1002")
        (field (name "DESIGNER") "TVBac")
      )
      (libsource (lib "Smartsocket") (part "RES; 10K; 0603; SMD; ESR03EZPF1002"))
    )
    (comp (ref "R4")
      (value "100R")
      (footprint "SMD-RES-0603-RS")
      (description "Res Thick Film 0603 100 Ohm 1% 0.1W(1/10W) ±100ppm/C Pad SMD T/R Automotive AEC-Q200")
      (fields
        (field (name "MANUFACTURER") "Rohm")
        (field (name "MANUFACTURER PART NUMBER") "KTR03EZPF1000")
        (field (name "DESIGNER") "TVBac")
      )
      (libsource (lib "Smartsocket") (part "RES; 100R; 0603; SMD; KTR03EZPF1000"))
    )
    (comp (ref "R5")
      (value "100R")
      (footprint "SMD-RES-0603-RS")
      (description "Res Thick Film 0603 100 Ohm 1% 0.1W(1/10W) ±100ppm/C Pad SMD T/R Automotive AEC-Q200")
      (fields
        (field (name "MANUFACTURER") "Rohm")
        (field (name "MANUFACTURER PART NUMBER") "KTR03EZPF1000")
        (field (name "DESIGNER") "TVBac")
      )
      (libsource (lib "Smartsocket") (part "RES; 100R; 0603; SMD; KTR03EZPF1000"))
    )
    (comp (ref "R6")
      (value "100R")
      (footprint "SMD-RES-0603-RS")
      (description "Res Thick Film 0603 100 Ohm 1% 0.1W(1/10W) ±100ppm/C Pad SMD T/R Automotive AEC-Q200")
      (fields
        (field (name "MANUFACTURER") "Rohm")
        (field (name "MANUFACTURER PART NUMBER") "KTR03EZPF1000")
        (field (name "DESIGNER") "TVBac")
      )
      (libsource (lib "Smartsocket") (part "RES; 100R; 0603; SMD; KTR03EZPF1000"))
    )
    (comp (ref "R7")
      (value "10mR")
      (footprint "SMD-RES-2512-VD")
      (description "Res Current Sense Metal Plate 2512 0.01 Ohm 1% 3W ±110ppm/°C Molded T/R")
      (fields
        (field (name "MANUFACTURER") "Vishay")
        (field (name "MANUFACTURER PART NUMBER") "WFMA2512R0100FEA")
        (field (name "DESIGNER") "TVBac")
      )
      (libsource (lib "Smartsocket") (part "RES; SHUNT; 10mOhm; SMD; WFMA2512R0100FEA"))
    )
    (comp (ref "R8")
      (value "10k")
      (footprint "SMD-RES-0603-SEI")
      (description "SMD Chip Resistor, 10 kOhm, ± 1%, 250 mW, 0603 [1608 Metric], Thick Film, Anti-Surge")
      (fields
        (field (name "MANUFACTURER") "Rohm")
        (field (name "MANUFACTURER PART NUMBER") "ESR03EZPF1002")
        (field (name "DESIGNER") "TVBac")
      )
      (libsource (lib "Resistors") (part "RES; 10K; 0603; SMD; ESR03EZPF1002"))
    )
    (comp (ref "R9")
      (value "100R")
      (footprint "SMD-RES-0603-RS")
      (description "Res Thick Film 0603 100 Ohm 1% 0.1W(1/10W) ±100ppm/C Pad SMD T/R Automotive AEC-Q200")
      (fields
        (field (name "MANUFACTURER") "Rohm")
        (field (name "MANUFACTURER PART NUMBER") "KTR03EZPF1000")
        (field (name "DESIGNER") "TVBac")
      )
      (libsource (lib "Resistors") (part "RES; 100R; 0603; SMD; KTR03EZPF1000"))
    )
    (comp (ref "R10")
      (value "1K")
      (footprint "SMD-RES-0603-SEI")
      (description "SMD Chip Resistor, 1 kOhm, ± 1%, 250 mW, 0603 [1608 Metric], Thick Film, Anti-Surge")
      (fields
        (field (name "MANUFACTURER") "Rohm")
        (field (name "MANUFACTURER PART NUMBER") "ESR03EZPF1001")
        (field (name "DESIGNER") "TVBac")
      )
      (libsource (lib "Resistors") (part "RES; 1K; 0603; SMD; ESR03EZPF1001"))
    )
    (comp (ref "R11")
      (value "100R")
      (footprint "SMD-RES-0603-RS")
      (description "Res Thick Film 0603 100 Ohm 1% 0.1W(1/10W) ±100ppm/C Pad SMD T/R Automotive AEC-Q200")
      (fields
        (field (name "MANUFACTURER") "Rohm")
        (field (name "MANUFACTURER PART NUMBER") "KTR03EZPF1000")
        (field (name "DESIGNER") "TVBac")
      )
      (libsource (lib "Resistors") (part "RES; 100R; 0603; SMD; KTR03EZPF1000"))
    )
    (comp (ref "R12")
      (value "1K")
      (footprint "SMD-RES-0603-SEI")
      (description "SMD Chip Resistor, 1 kOhm, ± 1%, 250 mW, 0603 [1608 Metric], Thick Film, Anti-Surge")
      (fields
        (field (name "MANUFACTURER") "Rohm")
        (field (name "MANUFACTURER PART NUMBER") "ESR03EZPF1001")
        (field (name "DESIGNER") "TVBac")
      )
      (libsource (lib "Resistors") (part "RES; 1K; 0603; SMD; ESR03EZPF1001"))
    )
    (comp (ref "R13")
      (value "1K")
      (footprint "SMD-RES-0603-SEI")
      (description "SMD Chip Resistor, 1 kOhm, ± 1%, 250 mW, 0603 [1608 Metric], Thick Film, Anti-Surge")
      (fields
        (field (name "MANUFACTURER") "Rohm")
        (field (name "MANUFACTURER PART NUMBER") "ESR03EZPF1001")
        (field (name "DESIGNER") "TVBac")
      )
      (libsource (lib "Resistors") (part "RES; 1K; 0603; SMD; ESR03EZPF1001"))
    )
    (comp (ref "R14")
      (value "300kR")
      (footprint "SMD-RES-0603-RS")
      (description "Res High Voltage Thick Film 0603 300k Ohm 1% 1/10W ±100ppm/°C Molded Paper T/R")
      (fields
        (field (name "MANUFACTURER") "Rohm")
        (field (name "MANUFACTURER PART NUMBER") "KTR03EZPF3003")
        (field (name "DESIGNER") "TVBac")
      )
      (libsource (lib "Resistors") (part "RES; 300K; 0603; SMD; KTR03EZPF3003"))
    )
    (comp (ref "R15")
      (value "300kR")
      (footprint "SMD-RES-0603-RS")
      (description "Res High Voltage Thick Film 0603 300k Ohm 1% 1/10W ±100ppm/°C Molded Paper T/R")
      (fields
        (field (name "MANUFACTURER") "Rohm")
        (field (name "MANUFACTURER PART NUMBER") "KTR03EZPF3003")
        (field (name "DESIGNER") "TVBac")
      )
      (libsource (lib "Resistors") (part "RES; 300K; 0603; SMD; KTR03EZPF3003"))
    )
    (comp (ref "R16")
      (value "300kR")
      (footprint "SMD-RES-0603-RS")
      (description "Res High Voltage Thick Film 0603 300k Ohm 1% 1/10W ±100ppm/°C Molded Paper T/R")
      (fields
        (field (name "MANUFACTURER") "Rohm")
        (field (name "MANUFACTURER PART NUMBER") "KTR03EZPF3003")
        (field (name "DESIGNER") "TVBac")
      )
      (libsource (lib "Resistors") (part "RES; 300K; 0603; SMD; KTR03EZPF3003"))
    )
    (comp (ref "R17")
      (value "1K")
      (footprint "SMD-RES-0603-SEI")
      (description "SMD Chip Resistor, 1 kOhm, ± 1%, 250 mW, 0603 [1608 Metric], Thick Film, Anti-Surge")
      (fields
        (field (name "MANUFACTURER") "Rohm")
        (field (name "MANUFACTURER PART NUMBER") "ESR03EZPF1001")
        (field (name "DESIGNER") "TVBac")
      )
      (libsource (lib "Resistors") (part "RES; 1K; 0603; SMD; ESR03EZPF1001"))
    )
    (comp (ref "R18")
      (value "300kR")
      (footprint "SMD-RES-0603-RS")
      (description "Res High Voltage Thick Film 0603 300k Ohm 1% 1/10W ±100ppm/°C Molded Paper T/R")
      (fields
        (field (name "MANUFACTURER") "Rohm")
        (field (name "MANUFACTURER PART NUMBER") "KTR03EZPF3003")
        (field (name "DESIGNER") "TVBac")
      )
      (libsource (lib "Resistors") (part "RES; 300K; 0603; SMD; KTR03EZPF3003"))
    )
    (comp (ref "R19")
      (value "100R")
      (footprint "SMD-RES-0603-RS")
      (description "Res Thick Film 0603 100 Ohm 1% 0.1W(1/10W) ±100ppm/C Pad SMD T/R Automotive AEC-Q200")
      (fields
        (field (name "MANUFACTURER") "Rohm")
        (field (name "MANUFACTURER PART NUMBER") "KTR03EZPF1000")
        (field (name "DESIGNER") "TVBac")
      )
      (libsource (lib "Resistors") (part "RES; 100R; 0603; SMD; KTR03EZPF1000"))
    )
    (comp (ref "R20")
      (value "10k")
      (footprint "SMD-RES-0603-SEI")
      (description "SMD Chip Resistor, 10 kOhm, ± 1%, 250 mW, 0603 [1608 Metric], Thick Film, Anti-Surge")
      (fields
        (field (name "MANUFACTURER") "Rohm")
        (field (name "MANUFACTURER PART NUMBER") "ESR03EZPF1002")
        (field (name "DESIGNER") "TVBac")
      )
      (libsource (lib "Resistors") (part "RES; 10K; 0603; SMD; ESR03EZPF1002"))
    )
    (comp (ref "R21")
      (value "100R")
      (footprint "SMD-RES-0603-RS")
      (description "Res Thick Film 0603 100 Ohm 1% 0.1W(1/10W) ±100ppm/C Pad SMD T/R Automotive AEC-Q200")
      (fields
        (field (name "MANUFACTURER") "Rohm")
        (field (name "MANUFACTURER PART NUMBER") "KTR03EZPF1000")
        (field (name "DESIGNER") "TVBac")
      )
      (libsource (lib "Resistors") (part "RES; 100R; 0603; SMD; KTR03EZPF1000"))
    )
    (comp (ref "R22")
      (value "100R")
      (footprint "SMD-RES-0603-RS")
      (description "Res Thick Film 0603 100 Ohm 1% 0.1W(1/10W) ±100ppm/C Pad SMD T/R Automotive AEC-Q200")
      (fields
        (field (name "MANUFACTURER") "Rohm")
        (field (name "MANUFACTURER PART NUMBER") "KTR03EZPF1000")
        (field (name "DESIGNER") "TVBac")
      )
      (libsource (lib "Resistors") (part "RES; 100R; 0603; SMD; KTR03EZPF1000"))
    )
    (comp (ref "R23")
      (value "10k")
      (footprint "SMD-RES-0603-SEI")
      (description "SMD Chip Resistor, 10 kOhm, ± 1%, 250 mW, 0603 [1608 Metric], Thick Film, Anti-Surge")
      (fields
        (field (name "MANUFACTURER") "Rohm")
        (field (name "MANUFACTURER PART NUMBER") "ESR03EZPF1002")
        (field (name "DESIGNER") "TVBac")
      )
      (libsource (lib "Resistors") (part "RES; 10K; 0603; SMD; ESR03EZPF1002"))
    )
    (comp (ref "R24")
      (value "10k")
      (footprint "SMD-RES-0603-SEI")
      (description "SMD Chip Resistor, 10 kOhm, ± 1%, 250 mW, 0603 [1608 Metric], Thick Film, Anti-Surge")
      (fields
        (field (name "MANUFACTURER") "Rohm")
        (field (name "MANUFACTURER PART NUMBER") "ESR03EZPF1002")
        (field (name "DESIGNER") "TVBac")
      )
      (libsource (lib "Resistors") (part "RES; 10K; 0603; SMD; ESR03EZPF1002"))
    )
    (comp (ref "R25")
      (value "10k")
      (footprint "SMD-RES-0603-SEI")
      (description "SMD Chip Resistor, 10 kOhm, ± 1%, 250 mW, 0603 [1608 Metric], Thick Film, Anti-Surge")
      (fields
        (field (name "MANUFACTURER") "Rohm")
        (field (name "MANUFACTURER PART NUMBER") "ESR03EZPF1002")
        (field (name "DESIGNER") "TVBac")
      )
      (libsource (lib "Resistors") (part "RES; 10K; 0603; SMD; ESR03EZPF1002"))
    )
    (comp (ref "R26")
      (value "4.7K")
      (footprint "SMD-RES-0603-RS")
      (description "Res Anti-Sulfured Thick Film 0603 4.7k Ohm 1% 1/10W ±100ppm/°C Molded Paper T/R")
      (fields
        (field (name "MANUFACTURER") "Rohm")
        (field (name "MANUFACTURER PART NUMBER") "SFR03EZPF4701")
        (field (name "DESIGNER") "TVBac")
      )
      (libsource (lib "Resistors") (part "RES; 4.7K; 0603; SMD; SFR03EZPF4701"))
    )
    (comp (ref "R27")
      (value "100R")
      (footprint "SMD-RES-0603-RS")
      (description "Res Thick Film 0603 100 Ohm 1% 0.1W(1/10W) ±100ppm/C Pad SMD T/R Automotive AEC-Q200")
      (fields
        (field (name "MANUFACTURER") "Rohm")
        (field (name "MANUFACTURER PART NUMBER") "KTR03EZPF1000")
        (field (name "DESIGNER") "TVBac")
      )
      (libsource (lib "Resistors") (part "RES; 100R; 0603; SMD; KTR03EZPF1000"))
    )
    (comp (ref "R28")
      (value "10k")
      (footprint "SMD-RES-0603-SEI")
      (description "SMD Chip Resistor, 10 kOhm, ± 1%, 250 mW, 0603 [1608 Metric], Thick Film, Anti-Surge")
      (fields
        (field (name "MANUFACTURER") "Rohm")
        (field (name "MANUFACTURER PART NUMBER") "ESR03EZPF1002")
        (field (name "DESIGNER") "TVBac")
      )
      (libsource (lib "Resistors") (part "RES; 10K; 0603; SMD; ESR03EZPF1002"))
    )
    (comp (ref "R29")
      (value "10k")
      (footprint "SMD-RES-0603-SEI")
      (description "SMD Chip Resistor, 10 kOhm, ± 1%, 250 mW, 0603 [1608 Metric], Thick Film, Anti-Surge")
      (fields
        (field (name "MANUFACTURER") "Rohm")
        (field (name "MANUFACTURER PART NUMBER") "ESR03EZPF1002")
        (field (name "DESIGNER") "TVBac")
      )
      (libsource (lib "Resistors") (part "RES; 10K; 0603; SMD; ESR03EZPF1002"))
    )
    (comp (ref "R30")
      (value "300kR")
      (footprint "SMD-RES-1206-RS")
      (description "Res Thick Film 1206 300K Ohm 1% 0.5W(1/2W) ±100ppm/C Epoxy Resin Pad SMD Automotive T/R")
      (fields
        (field (name "MANUFACTURER") "Rohm")
        (field (name "MANUFACTURER PART NUMBER") "ESR18EZPF3003")
        (field (name "DESIGNER") "TVBac")
      )
      (libsource (lib "Resistors") (part "RES; 300K; 1206; ESR18EZPF3003"))
    )
    (comp (ref "R31")
      (value "100R")
      (footprint "SMD-RES-0603-RS")
      (description "Res Thick Film 0603 100 Ohm 1% 0.1W(1/10W) ±100ppm/C Pad SMD T/R Automotive AEC-Q200")
      (fields
        (field (name "MANUFACTURER") "Rohm")
        (field (name "MANUFACTURER PART NUMBER") "KTR03EZPF1000")
        (field (name "DESIGNER") "TVBac")
      )
      (libsource (lib "Resistors") (part "RES; 100R; 0603; SMD; KTR03EZPF1000"))
    )
    (comp (ref "R32")
      (value "100R")
      (footprint "SMD-RES-0603-RS")
      (description "Res Thick Film 0603 100 Ohm 1% 0.1W(1/10W) ±100ppm/C Pad SMD T/R Automotive AEC-Q200")
      (fields
        (field (name "MANUFACTURER") "Rohm")
        (field (name "MANUFACTURER PART NUMBER") "KTR03EZPF1000")
        (field (name "DESIGNER") "TVBac")
      )
      (libsource (lib "Resistors") (part "RES; 100R; 0603; SMD; KTR03EZPF1000"))
    )
    (comp (ref "R33")
      (value "4.7K")
      (footprint "SMD-RES-0603-RS")
      (description "Res Anti-Sulfured Thick Film 0603 4.7k Ohm 1% 1/10W ±100ppm/°C Molded Paper T/R")
      (fields
        (field (name "MANUFACTURER") "Rohm")
        (field (name "MANUFACTURER PART NUMBER") "SFR03EZPF4701")
        (field (name "DESIGNER") "TVBac")
      )
      (libsource (lib "Resistors") (part "RES; 4.7K; 0603; SMD; SFR03EZPF4701"))
    )
    (comp (ref "R34")
      (value "4.7K")
      (footprint "SMD-RES-0603-RS")
      (description "Res Anti-Sulfured Thick Film 0603 4.7k Ohm 1% 1/10W ±100ppm/°C Molded Paper T/R")
      (fields
        (field (name "MANUFACTURER") "Rohm")
        (field (name "MANUFACTURER PART NUMBER") "SFR03EZPF4701")
        (field (name "DESIGNER") "TVBac")
      )
      (libsource (lib "Resistors") (part "RES; 4.7K; 0603; SMD; SFR03EZPF4701"))
    )
    (comp (ref "R35")
      (value "1K")
      (footprint "SMD-RES-0603-SEI")
      (description "SMD Chip Resistor, 1 kOhm, ± 1%, 250 mW, 0603 [1608 Metric], Thick Film, Anti-Surge")
      (fields
        (field (name "MANUFACTURER") "Rohm")
        (field (name "MANUFACTURER PART NUMBER") "ESR03EZPF1001")
        (field (name "DESIGNER") "TVBac")
      )
      (libsource (lib "Resistors") (part "RES; 1K; 0603; SMD; ESR03EZPF1001"))
    )
    (comp (ref "R36")
      (value "100K")
      (footprint "SMD-RES-0603-SEI")
      (description "Res Thick Film 0603 100K Ohm 5% 0.25W(1/4W) ±200ppm/C Pad SMD Automotive T/R")
      (fields
        (field (name "MANUFACTURER") "Rohm")
        (field (name "MANUFACTURER PART NUMBER") "ESR03EZPJ104")
        (field (name "DESIGNER") "TVBac")
      )
      (libsource (lib "Resistors") (part "RES; 100K; 0603; SMD; ESR03EZPJ104"))
    )
    (comp (ref "R37")
      (value "1K")
      (footprint "SMD-RES-0603-SEI")
      (description "SMD Chip Resistor, 1 kOhm, ± 1%, 250 mW, 0603 [1608 Metric], Thick Film, Anti-Surge")
      (fields
        (field (name "MANUFACTURER") "Rohm")
        (field (name "MANUFACTURER PART NUMBER") "ESR03EZPF1001")
        (field (name "DESIGNER") "TVBac")
      )
      (libsource (lib "Resistors") (part "RES; 1K; 0603; SMD; ESR03EZPF1001"))
    )
    (comp (ref "R38")
      (value "1K")
      (footprint "SMD-RES-0603-SEI")
      (description "SMD Chip Resistor, 1 kOhm, ± 1%, 250 mW, 0603 [1608 Metric], Thick Film, Anti-Surge")
      (fields
        (field (name "MANUFACTURER") "Rohm")
        (field (name "MANUFACTURER PART NUMBER") "ESR03EZPF1001")
        (field (name "DESIGNER") "TVBac")
      )
      (libsource (lib "Resistors") (part "RES; 1K; 0603; SMD; ESR03EZPF1001"))
    )
    (comp (ref "R39")
      (value "10k")
      (footprint "SMD-RES-0603-SEI")
      (description "SMD Chip Resistor, 10 kOhm, ± 1%, 250 mW, 0603 [1608 Metric], Thick Film, Anti-Surge")
      (fields
        (field (name "MANUFACTURER") "Rohm")
        (field (name "MANUFACTURER PART NUMBER") "ESR03EZPF1002")
        (field (name "DESIGNER") "TVBac")
      )
      (libsource (lib "Resistors") (part "RES; 10K; 0603; SMD; ESR03EZPF1002"))
    )
    (comp (ref "R40")
      (value "1K")
      (footprint "SMD-RES-0603-SEI")
      (description "SMD Chip Resistor, 1 kOhm, ± 1%, 250 mW, 0603 [1608 Metric], Thick Film, Anti-Surge")
      (fields
        (field (name "MANUFACTURER") "Rohm")
        (field (name "MANUFACTURER PART NUMBER") "ESR03EZPF1001")
        (field (name "DESIGNER") "TVBac")
      )
      (libsource (lib "Resistors") (part "RES; 1K; 0603; SMD; ESR03EZPF1001"))
    )
    (comp (ref "R41")
      (value "100K")
      (footprint "SMD-RES-0603-SEI")
      (description "Res Thick Film 0603 100K Ohm 5% 0.25W(1/4W) ±200ppm/C Pad SMD Automotive T/R")
      (fields
        (field (name "MANUFACTURER") "Rohm")
        (field (name "MANUFACTURER PART NUMBER") "ESR03EZPJ104")
        (field (name "DESIGNER") "TVBac")
      )
      (libsource (lib "Resistors") (part "RES; 100K; 0603; SMD; ESR03EZPJ104"))
    )
    (comp (ref "R42")
      (value "1K")
      (footprint "SMD-RES-0603-SEI")
      (description "SMD Chip Resistor, 1 kOhm, ± 1%, 250 mW, 0603 [1608 Metric], Thick Film, Anti-Surge")
      (fields
        (field (name "MANUFACTURER") "Rohm")
        (field (name "MANUFACTURER PART NUMBER") "ESR03EZPF1001")
        (field (name "DESIGNER") "TVBac")
      )
      (libsource (lib "Resistors") (part "RES; 1K; 0603; SMD; ESR03EZPF1001"))
    )
    (comp (ref "R43")
      (value "1K")
      (footprint "SMD-RES-0603-SEI")
      (description "SMD Chip Resistor, 1 kOhm, ± 1%, 250 mW, 0603 [1608 Metric], Thick Film, Anti-Surge")
      (fields
        (field (name "MANUFACTURER") "Rohm")
        (field (name "MANUFACTURER PART NUMBER") "ESR03EZPF1001")
        (field (name "DESIGNER") "TVBac")
      )
      (libsource (lib "Resistors") (part "RES; 1K; 0603; SMD; ESR03EZPF1001"))
    )
    (comp (ref "R44")
      (value "100K")
      (footprint "SMD-RES-0603-SEI")
      (description "Res Thick Film 0603 100K Ohm 5% 0.25W(1/4W) ±200ppm/C Pad SMD Automotive T/R")
      (fields
        (field (name "MANUFACTURER") "Rohm")
        (field (name "MANUFACTURER PART NUMBER") "ESR03EZPJ104")
        (field (name "DESIGNER") "TVBac")
      )
      (libsource (lib "Resistors") (part "RES; 100K; 0603; SMD; ESR03EZPJ104"))
    )
    (comp (ref "R45")
      (value "100K")
      (footprint "SMD-RES-0603-SEI")
      (description "Res Thick Film 0603 100K Ohm 5% 0.25W(1/4W) ±200ppm/C Pad SMD Automotive T/R")
      (fields
        (field (name "MANUFACTURER") "Rohm")
        (field (name "MANUFACTURER PART NUMBER") "ESR03EZPJ104")
        (field (name "DESIGNER") "TVBac")
      )
      (libsource (lib "Resistors") (part "RES; 100K; 0603; SMD; ESR03EZPJ104"))
    )
    (comp (ref "R46")
      (value "1K")
      (footprint "SMD-RES-0603-SEI")
      (description "SMD Chip Resistor, 1 kOhm, ± 1%, 250 mW, 0603 [1608 Metric], Thick Film, Anti-Surge")
      (fields
        (field (name "MANUFACTURER") "Rohm")
        (field (name "MANUFACTURER PART NUMBER") "ESR03EZPF1001")
        (field (name "DESIGNER") "TVBac")
      )
      (libsource (lib "Resistors") (part "RES; 1K; 0603; SMD; ESR03EZPF1001"))
    )
    (comp (ref "R47")
      (value "1K")
      (footprint "SMD-RES-0603-SEI")
      (description "SMD Chip Resistor, 1 kOhm, ± 1%, 250 mW, 0603 [1608 Metric], Thick Film, Anti-Surge")
      (fields
        (field (name "MANUFACTURER") "Rohm")
        (field (name "MANUFACTURER PART NUMBER") "ESR03EZPF1001")
        (field (name "DESIGNER") "TVBac")
      )
      (libsource (lib "Resistors") (part "RES; 1K; 0603; SMD; ESR03EZPF1001"))
    )
    (comp (ref "R48")
      (value "100K")
      (footprint "SMD-RES-0603-SEI")
      (description "Res Thick Film 0603 100K Ohm 5% 0.25W(1/4W) ±200ppm/C Pad SMD Automotive T/R")
      (fields
        (field (name "MANUFACTURER") "Rohm")
        (field (name "MANUFACTURER PART NUMBER") "ESR03EZPJ104")
        (field (name "DESIGNER") "TVBac")
      )
      (libsource (lib "Resistors") (part "RES; 100K; 0603; SMD; ESR03EZPJ104"))
    )
    (comp (ref "R49")
      (value "1K")
      (footprint "SMD-RES-0603-SEI")
      (description "SMD Chip Resistor, 1 kOhm, ± 1%, 250 mW, 0603 [1608 Metric], Thick Film, Anti-Surge")
      (fields
        (field (name "MANUFACTURER") "Rohm")
        (field (name "MANUFACTURER PART NUMBER") "ESR03EZPF1001")
        (field (name "DESIGNER") "TVBac")
      )
      (libsource (lib "Resistors") (part "RES; 1K; 0603; SMD; ESR03EZPF1001"))
    )
    (comp (ref "R54")
      (value "1K")
      (footprint "SMD-RES-0603-SEI")
      (description "SMD Chip Resistor, 1 kOhm, ± 1%, 250 mW, 0603 [1608 Metric], Thick Film, Anti-Surge")
      (fields
        (field (name "MANUFACTURER") "Rohm")
        (field (name "MANUFACTURER PART NUMBER") "ESR03EZPF1001")
        (field (name "DESIGNER") "TVBac")
      )
      (libsource (lib "Resistors") (part "RES; 1K; 0603; SMD; ESR03EZPF1001"))
    )
    (comp (ref "R55")
      (value "1K")
      (footprint "SMD-RES-0603-SEI")
      (description "SMD Chip Resistor, 1 kOhm, ± 1%, 250 mW, 0603 [1608 Metric], Thick Film, Anti-Surge")
      (fields
        (field (name "MANUFACTURER") "Rohm")
        (field (name "MANUFACTURER PART NUMBER") "ESR03EZPF1001")
        (field (name "DESIGNER") "TVBac")
      )
      (libsource (lib "Smartsocket") (part "RES; 1K; 0603; SMD; ESR03EZPF1001"))
    )
    (comp (ref "R56")
      (value "1K")
      (footprint "SMD-RES-0603-SEI")
      (description "SMD Chip Resistor, 1 kOhm, ± 1%, 250 mW, 0603 [1608 Metric], Thick Film, Anti-Surge")
      (fields
        (field (name "MANUFACTURER") "Rohm")
        (field (name "MANUFACTURER PART NUMBER") "ESR03EZPF1001")
        (field (name "DESIGNER") "TVBac")
      )
      (libsource (lib "Resistors") (part "RES; 1K; 0603; SMD; ESR03EZPF1001"))
    )
    (comp (ref "R57")
      (value "10mR")
      (footprint "SMD-RES-2512-VD")
      (description "Res Current Sense Metal Plate 2512 0.01 Ohm 1% 3W ±110ppm/°C Molded T/R")
      (fields
        (field (name "MANUFACTURER") "Vishay")
        (field (name "MANUFACTURER PART NUMBER") "WFMA2512R0100FEA")
        (field (name "DESIGNER") "TVBac")
      )
      (libsource (lib "Smartsocket") (part "RES; SHUNT; 10mOhm; SMD; WFMA2512R0100FEA"))
    )
    (comp (ref "R58")
      (value "1K")
      (footprint "SMD-RES-0603-SEI")
      (description "SMD Chip Resistor, 1 kOhm, ± 1%, 250 mW, 0603 [1608 Metric], Thick Film, Anti-Surge")
      (fields
        (field (name "MANUFACTURER") "Rohm")
        (field (name "MANUFACTURER PART NUMBER") "ESR03EZPF1001")
        (field (name "DESIGNER") "TVBac")
      )
      (libsource (lib "Smartsocket") (part "RES; 1K; 0603; SMD; ESR03EZPF1001"))
    )
    (comp (ref "SW1")
      (value "https://www.digikey.com/en/products/detail/panasonic-electronic-components/EVQ-P7L01P/4429453")
      (footprint "SW-HxLxW-1.1x3.5x2.9-PEC")
      (description "Tactile Switch SPST-NO Side Actuated Surface Mount, Right Angle")
      (fields (field (name "MP") "EVQ-P7L01P") (field (name "MF") "Panasonic Electronic Components"))
      (libsource (lib "") (part "BUT; SW; SMD; EVQ-P7L01P_1"))
    )
    (comp (ref "SW2")
      (value "https://www.digikey.com/en/products/detail/panasonic-electronic-components/EVQ-P7L01P/4429453")
      (footprint "SW-HxLxW-1.1x3.5x2.9-PEC")
      (description "Tactile Switch SPST-NO Side Actuated Surface Mount, Right Angle")
      (fields (field (name "MP") "EVQ-P7L01P") (field (name "MF") "Panasonic Electronic Components"))
      (libsource (lib "Button") (part "BUT; SW; SMD; EVQ-P7L01P"))
    )
    (comp (ref "SW3")
      (value "Tactile Switch SPST-NO Top Actuated Surface Mount")
      (footprint "SW-HxLxW-5.0x6.0x3.5-C&K")
      (description "Switch Tactile N.O. SPST Rectangular Button J-Bend 0.05A 12VDC 1.77N SMD T/R")
      (fields
        (field (name "MANUFACTURER") "ITT C&K")
        (field (name "MANUFACTURER PART NUMBER") "PTS636SM50JSMTRLFS")
      )
      (libsource (lib "Button") (part "BUT; SW; SMD; PTS636SM50JSMTRLFS"))
    )
    (comp (ref "T1")
      (value "For SMPS Transformer 500VAC Isolation Through Hole")
      (footprint "EE13 - POWER")
      (description "OFFLINE TRANSFORMER 6W EE13/7/6")
      (fields (field (name "MF") "Wurth Electronics Inc") (field (name "MP") "EE13/6/6"))
      (libsource (lib "Transformer") (part "EE13/6/6-Power"))
    )
    (comp (ref "VR1")
      (value "470 V 8 kA Varistor 1 Circuit Through Hole Disc 20mm")
      (footprint "VARISTOR-ETE")
      (description "Epcos St&ard Series Metal Oxide Varistor 580pF 100A; Clamping 775V; Varistor 470V")
      (fields
        (field (name "MANUFACTURER") "TDK EPCOS")
        (field (name "MANUFACTURER PART NUMBER") "B72220S0301K101")
        (field (name "DESIGNER") "TVBac")
      )
      (libsource (lib "Smartsocket") (part "VAR; 470V; 100A; B72220S0301K101"))
    )
    (comp (ref "X1")
      (value "3.58M")
      (footprint "SMD-HC-49/US-ALLC")
      (description "Crystal 3.579545MHz ±20ppm (Tol) ±50ppm (Stability) 18pF FUND 180Ohm 2-Pin HC-49/US SMD T/R")
      (fields
        (field (name "MANUFACTURER") "Abracon")
        (field (name "MANUFACTURER PART NUMBER") "ABLS-3.579545MHZ-B2-T")
        (field (name "DESIGNER") "TVBac")
      )
      (libsource (lib "Oscillators") (part "OSC; 3.58M; 3.579545M; ABLS-3.579545MHZ-B2-T"))
    )
  )
  (nets
    (net (code "1") (name "+5") (class "Default")
      (node (ref "C26") (pin "2") (pinfunction "2_2") (pintype "passive"))
      (node (ref "C27") (pin "1") (pinfunction "1_1") (pintype "passive"))
      (node (ref "C5") (pin "1") (pinfunction "1_1") (pintype "passive"))
      (node (ref "C6") (pin "1") (pinfunction "1_1") (pintype "passive"))
      (node (ref "C8") (pin "2") (pinfunction "2_2") (pintype "passive"))
      (node (ref "C9") (pin "2") (pinfunction "2_2") (pintype "passive"))
      (node (ref "IC1") (pin "4") (pinfunction "VCC_4") (pintype "power_in"))
      (node (ref "IC2") (pin "1") (pinfunction "~{RESET}_1") (pintype "passive"))
      (node (ref "IC2") (pin "2") (pinfunction "DVDD_2") (pintype "passive"))
      (node (ref "IC2") (pin "3") (pinfunction "AVDD_3") (pintype "passive"))
      (node (ref "IC8") (pin "3") (pinfunction "IN_3") (pintype "passive"))
      (node (ref "IC9") (pin "3") (pinfunction "OUT_3") (pintype "passive"))
      (node (ref "R39") (pin "2") (pinfunction "2_2") (pintype "passive"))
    )
    (net (code "2") (name "+12") (class "Default")
      (node (ref "C1") (pin "1") (pinfunction "1_1") (pintype "passive"))
      (node (ref "D4") (pin "1") (pinfunction "K_1") (pintype "passive"))
      (node (ref "D5") (pin "K") (pinfunction "K_K") (pintype "passive"))
      (node (ref "IC9") (pin "1") (pinfunction "IN_1") (pintype "passive"))
      (node (ref "K1") (pin "2") (pinfunction "COIL2_2") (pintype "passive"))
      (node (ref "K2") (pin "1") (pinfunction "COIL1_1") (pintype "passive"))
      (node (ref "R27") (pin "2") (pinfunction "2_2") (pintype "passive"))
      (node (ref "R28") (pin "2") (pinfunction "2_2") (pintype "passive"))
    )
    (net (code "3") (name "/ADE-CF") (class "Default")
      (node (ref "M1") (pin "36") (pinfunction "IO22_36") (pintype "passive"))
      (node (ref "R25") (pin "2") (pinfunction "2_2") (pintype "passive"))
      (node (ref "R34") (pin "2") (pinfunction "2_2") (pintype "passive"))
    )
    (net (code "4") (name "/ADE-MISO") (class "Default")
      (node (ref "M1") (pin "26") (pinfunction "IO4_26") (pintype "passive"))
      (node (ref "R23") (pin "2") (pinfunction "2_2") (pintype "passive"))
      (node (ref "R26") (pin "2") (pinfunction "2_2") (pintype "passive"))
    )
    (net (code "5") (name "/ADE-MOSI") (class "Default")
      (node (ref "M1") (pin "29") (pinfunction "IO5_29") (pintype "passive"))
      (node (ref "R19") (pin "2") (pinfunction "2_2") (pintype "passive"))
    )
    (net (code "6") (name "/ADE-SCLK") (class "Default")
      (node (ref "M1") (pin "24") (pinfunction "IO2_24") (pintype "passive"))
      (node (ref "R21") (pin "2") (pinfunction "2_2") (pintype "passive"))
    )
    (net (code "7") (name "/ADE-ZX") (class "Default")
      (node (ref "M1") (pin "33") (pinfunction "IO21_33") (pintype "passive"))
      (node (ref "R24") (pin "2") (pinfunction "2_2") (pintype "passive"))
      (node (ref "R33") (pin "2") (pinfunction "2_2") (pintype "passive"))
    )
    (net (code "8") (name "/ADE-~{CS}") (class "Default")
      (node (ref "M1") (pin "23") (pinfunction "IO15_23") (pintype "passive"))
      (node (ref "R22") (pin "2") (pinfunction "2_2") (pintype "passive"))
    )
    (net (code "9") (name "/ADE-~{IQR}") (class "Default")
      (node (ref "IC2") (pin "14") (pinfunction "~{IRQ}_14") (pintype "passive"))
      (node (ref "R31") (pin "1") (pinfunction "1_1") (pintype "passive"))
      (node (ref "R8") (pin "2") (pinfunction "2_2") (pintype "passive"))
    )
    (net (code "10") (name "/ADE-~{SAG}") (class "Default")
      (node (ref "IC2") (pin "13") (pinfunction "~{SAG}_13") (pintype "passive"))
      (node (ref "R20") (pin "2") (pinfunction "2_2") (pintype "passive"))
      (node (ref "R32") (pin "1") (pinfunction "1_1") (pintype "passive"))
    )
    (net (code "11") (name "/CUR-SHT-1") (class "Default")
      (node (ref "D3") (pin "AC1") (pinfunction "AC1_AC1") (pintype "passive"))
      (node (ref "K2") (pin "3") (pinfunction "COM_3") (pintype "passive"))
      (node (ref "R57") (pin "2") (pinfunction "2_2") (pintype "passive"))
      (node (ref "R7") (pin "2") (pinfunction "2_2") (pintype "passive"))
      (node (ref "R9") (pin "1") (pinfunction "1_1") (pintype "passive"))
    )
    (net (code "12") (name "/ESP-~{IQR}") (class "Default")
      (node (ref "M1") (pin "30") (pinfunction "IO18_30") (pintype "passive"))
      (node (ref "R31") (pin "2") (pinfunction "2_2") (pintype "passive"))
    )
    (net (code "13") (name "/ESP-~{SAG}") (class "Default")
      (node (ref "M1") (pin "31") (pinfunction "IO19_31") (pintype "passive"))
      (node (ref "R32") (pin "2") (pinfunction "2_2") (pintype "passive"))
    )
    (net (code "14") (name "/LEAK") (class "Default")
      (node (ref "C20") (pin "2") (pinfunction "2_2") (pintype "passive"))
      (node (ref "D7") (pin "K") (pinfunction "K_K") (pintype "passive"))
      (node (ref "D8") (pin "K") (pinfunction "K_K") (pintype "passive"))
      (node (ref "IC1") (pin "6") (pinfunction "2IN-_6") (pintype "passive"))
      (node (ref "M1") (pin "16") (pinfunction "IO13_16") (pintype "passive"))
      (node (ref "R42") (pin "1") (pinfunction "1_1") (pintype "passive"))
      (node (ref "R45") (pin "2") (pinfunction "2_2") (pintype "passive"))
    )
    (net (code "15") (name "/LEAK_INT") (class "Default")
      (node (ref "M1") (pin "13") (pinfunction "IO14_13") (pintype "passive"))
      (node (ref "R54") (pin "2") (pinfunction "2_2") (pintype "passive"))
      (node (ref "R56") (pin "2") (pinfunction "2_2") (pintype "passive"))
    )
    (net (code "16") (name "/LED-B") (class "Default")
      (node (ref "D1") (pin "6") (pinfunction "B_A_6") (pintype "passive"))
      (node (ref "M1") (pin "8") (pinfunction "IO32_8") (pintype "passive"))
    )
    (net (code "17") (name "/LED-G") (class "Default")
      (node (ref "D1") (pin "4") (pinfunction "G_A_4") (pintype "passive"))
      (node (ref "M1") (pin "10") (pinfunction "IO25_10") (pintype "passive"))
    )
    (net (code "18") (name "/LED-R") (class "Default")
      (node (ref "D1") (pin "5") (pinfunction "R_A_5") (pintype "passive"))
      (node (ref "M1") (pin "9") (pinfunction "IO33_9") (pintype "passive"))
    )
    (net (code "19") (name "/OFF_RELAY") (class "Default")
      (node (ref "IC1") (pin "1") (pinfunction "1OUT_1") (pintype "passive"))
      (node (ref "R54") (pin "1") (pinfunction "1_1") (pintype "passive"))
      (node (ref "R58") (pin "1") (pinfunction "1_1") (pintype "passive"))
    )
    (net (code "20") (name "/POWER-300V") (class "Default")
      (node (ref "C4") (pin "1") (pinfunction "1_1") (pintype "passive"))
      (node (ref "D3") (pin "POS") (pinfunction "POS_POS") (pintype "passive"))
      (node (ref "L1") (pin "1") (pinfunction "1_1") (pintype "passive"))
    )
    (net (code "21") (name "/POWER-300V-R") (class "Default")
      (node (ref "C22") (pin "2") (pinfunction "2_2") (pintype "passive"))
      (node (ref "C3") (pin "1") (pinfunction "1_1") (pintype "passive"))
      (node (ref "L1") (pin "2") (pinfunction "2_2") (pintype "passive"))
      (node (ref "R30") (pin "2") (pinfunction "2_2") (pintype "passive"))
      (node (ref "T1") (pin "6") (pinfunction "6_6") (pintype "passive"))
    )
    (net (code "22") (name "/POWER-GND") (class "Default")
      (node (ref "C4") (pin "2") (pinfunction "2_2") (pintype "passive"))
      (node (ref "D3") (pin "NEG") (pinfunction "NEG_NEG") (pintype "passive"))
      (node (ref "L2") (pin "1") (pinfunction "1_1") (pintype "passive"))
    )
    (net (code "23") (name "/POWER-GND-R") (class "Default")
      (node (ref "C2") (pin "2") (pinfunction "2_2") (pintype "passive"))
      (node (ref "C3") (pin "2") (pinfunction "2_2") (pintype "passive"))
      (node (ref "IC3") (pin "1") (pinfunction "S_1") (pintype "passive"))
      (node (ref "IC3") (pin "2") (pinfunction "S_2") (pintype "passive"))
      (node (ref "IC3") (pin "7") (pinfunction "S_7") (pintype "passive"))
      (node (ref "IC3") (pin "8") (pinfunction "S_8") (pintype "passive"))
      (node (ref "L2") (pin "2") (pinfunction "2_2") (pintype "passive"))
    )
    (net (code "24") (name "/POWER_N") (class "Default")
      (node (ref "F1") (pin "2") (pinfunction "2_2") (pintype "passive"))
      (node (ref "F2") (pin "1") (pinfunction "1_1") (pintype "passive"))
      (node (ref "K1") (pin "4") (pinfunction "NO_4") (pintype "passive"))
      (node (ref "R18") (pin "1") (pinfunction "1_1") (pintype "passive"))
      (node (ref "VR1") (pin "2") (pinfunction "2_2") (pintype "passive"))
    )
    (net (code "25") (name "/RELAY") (class "Default")
      (node (ref "M1") (pin "37") (pinfunction "IO23_37") (pintype "passive"))
      (node (ref "R55") (pin "1") (pinfunction "1_1") (pintype "passive"))
    )
    (net (code "26") (name "/RXD0") (class "Default")
      (node (ref "J1") (pin "02") (pinfunction "2_02") (pintype "passive"))
      (node (ref "M1") (pin "34") (pinfunction "RXD0_34") (pintype "passive"))
    )
    (net (code "27") (name "/TXD0") (class "Default")
      (node (ref "J1") (pin "03") (pinfunction "2_03") (pintype "passive"))
      (node (ref "M1") (pin "35") (pinfunction "TXD0_35") (pintype "passive"))
    )
    (net (code "28") (name "3V3-ESP") (class "Default")
      (node (ref "C25") (pin "2") (pinfunction "2_2") (pintype "passive"))
      (node (ref "C28") (pin "2") (pinfunction "2_2") (pintype "passive"))
      (node (ref "C7") (pin "1") (pinfunction "1_1") (pintype "passive"))
      (node (ref "IC8") (pin "4") (pinfunction "OUT_4") (pintype "passive"))
      (node (ref "J1") (pin "01") (pinfunction "1_01") (pintype "passive"))
      (node (ref "M1") (pin "2") (pinfunction "3V3_2") (pintype "passive"))
      (node (ref "R1") (pin "2") (pinfunction "2_2") (pintype "passive"))
      (node (ref "R20") (pin "1") (pinfunction "1_1") (pintype "passive"))
      (node (ref "R3") (pin "2") (pinfunction "2_2") (pintype "passive"))
      (node (ref "R8") (pin "1") (pinfunction "1_1") (pintype "passive"))
    )
    (net (code "29") (name "GND") (class "Default")
      (node (ref "C1") (pin "2") (pinfunction "2_2") (pintype "passive"))
      (node (ref "C10") (pin "2") (pinfunction "2_2") (pintype "passive"))
      (node (ref "C11") (pin "1") (pinfunction "1_1") (pintype "passive"))
      (node (ref "C12") (pin "1") (pinfunction "1_1") (pintype "passive"))
      (node (ref "C13") (pin "1") (pinfunction "1_1") (pintype "passive"))
      (node (ref "C14") (pin "1") (pinfunction "1_1") (pintype "passive"))
      (node (ref "C15") (pin "1") (pinfunction "1_1") (pintype "passive"))
      (node (ref "C16") (pin "1") (pinfunction "1_1") (pintype "passive"))
      (node (ref "C17") (pin "2") (pinfunction "2_2") (pintype "passive"))
      (node (ref "C18") (pin "1") (pinfunction "1_1") (pintype "passive"))
      (node (ref "C19") (pin "1") (pinfunction "1_1") (pintype "passive"))
      (node (ref "C20") (pin "1") (pinfunction "1_1") (pintype "passive"))
      (node (ref "C21") (pin "1") (pinfunction "1_1") (pintype "passive"))
      (node (ref "C23") (pin "2") (pinfunction "2_2") (pintype "passive"))
      (node (ref "C24") (pin "1") (pinfunction "1_1") (pintype "passive"))
      (node (ref "C25") (pin "1") (pinfunction "1_1") (pintype "passive"))
      (node (ref "C26") (pin "1") (pinfunction "1_1") (pintype "passive"))
      (node (ref "C27") (pin "2") (pinfunction "2_2") (pintype "passive"))
      (node (ref "C28") (pin "1") (pinfunction "1_1") (pintype "passive"))
      (node (ref "C29") (pin "1") (pinfunction "1_1") (pintype "passive"))
      (node (ref "C5") (pin "2") (pinfunction "2_2") (pintype "passive"))
      (node (ref "C6") (pin "2") (pinfunction "2_2") (pintype "passive"))
      (node (ref "C7") (pin "2") (pinfunction "2_2") (pintype "passive"))
      (node (ref "C8") (pin "1") (pinfunction "1_1") (pintype "passive"))
      (node (ref "C9") (pin "1") (pinfunction "1_1") (pintype "passive"))
      (node (ref "IC1") (pin "11") (pinfunction "GND_11") (pintype "power_in"))
      (node (ref "IC2") (pin "10") (pinfunction "DGND_10") (pintype "passive"))
      (node (ref "IC2") (pin "8") (pinfunction "AGND_8") (pintype "passive"))
      (node (ref "IC4") (pin "3") (pinfunction "ANODE_3") (pintype "passive"))
      (node (ref "IC8") (pin "1") (pinfunction "ADJ/GND_1") (pintype "passive"))
      (node (ref "IC9") (pin "2") (pinfunction "GND_2") (pintype "passive"))
      (node (ref "IN2") (pin "1") (pinfunction "IN_1") (pintype "passive"))
      (node (ref "J1") (pin "04") (pinfunction "4_04") (pintype "passive"))
      (node (ref "M1") (pin "1") (pinfunction "GND_1") (pintype "passive"))
      (node (ref "M1") (pin "15") (pinfunction "GND_15") (pintype "passive"))
      (node (ref "M1") (pin "38") (pinfunction "GND_38") (pintype "passive"))
      (node (ref "M1") (pin "39") (pinfunction "GND_39") (pintype "passive"))
      (node (ref "Q2") (pin "2") (pinfunction "E_2") (pintype "passive"))
      (node (ref "Q3") (pin "2") (pinfunction "E_2") (pintype "passive"))
      (node (ref "R11") (pin "1") (pinfunction "1_1") (pintype "passive"))
      (node (ref "R13") (pin "1") (pinfunction "1_1") (pintype "passive"))
      (node (ref "R17") (pin "1") (pinfunction "1_1") (pintype "passive"))
      (node (ref "R23") (pin "1") (pinfunction "1_1") (pintype "passive"))
      (node (ref "R24") (pin "1") (pinfunction "1_1") (pintype "passive"))
      (node (ref "R25") (pin "1") (pinfunction "1_1") (pintype "passive"))
      (node (ref "R29") (pin "1") (pinfunction "1_1") (pintype "passive"))
      (node (ref "R38") (pin "1") (pinfunction "1_1") (pintype "passive"))
      (node (ref "R4") (pin "2") (pinfunction "2_2") (pintype "passive"))
      (node (ref "R41") (pin "2") (pinfunction "2_2") (pintype "passive"))
      (node (ref "R45") (pin "1") (pinfunction "1_1") (pintype "passive"))
      (node (ref "R48") (pin "2") (pinfunction "2_2") (pintype "passive"))
      (node (ref "R5") (pin "2") (pinfunction "2_2") (pintype "passive"))
      (node (ref "R56") (pin "1") (pinfunction "1_1") (pintype "passive"))
      (node (ref "R57") (pin "1") (pinfunction "1_1") (pintype "passive"))
      (node (ref "R6") (pin "2") (pinfunction "2_2") (pintype "passive"))
      (node (ref "R7") (pin "1") (pinfunction "1_1") (pintype "passive"))
      (node (ref "SW1") (pin "11") (pinfunction "1_11") (pintype "passive"))
      (node (ref "SW2") (pin "11") (pinfunction "1_11") (pintype "passive"))
      (node (ref "SW3") (pin "2") (pinfunction "NO_2") (pintype "passive"))
      (node (ref "T1") (pin "1") (pinfunction "1_1") (pintype "passive"))
      (node (ref "T1") (pin "10") (pinfunction "10_10") (pintype "passive"))
      (node (ref "VR1") (pin "1") (pinfunction "1_1") (pintype "passive"))
    )
    (net (code "30") (name "Net-(C11-Pad2)") (class "Default")
      (node (ref "C11") (pin "2") (pinfunction "2_2") (pintype "passive"))
      (node (ref "R10") (pin "1") (pinfunction "1_1") (pintype "passive"))
      (node (ref "R9") (pin "2") (pinfunction "2_2") (pintype "passive"))
    )
    (net (code "31") (name "Net-(C14-Pad2)") (class "Default")
      (node (ref "C14") (pin "2") (pinfunction "2_2") (pintype "passive"))
      (node (ref "R11") (pin "2") (pinfunction "2_2") (pintype "passive"))
      (node (ref "R12") (pin "1") (pinfunction "1_1") (pintype "passive"))
    )
    (net (code "32") (name "Net-(C22-Pad1)") (class "Default")
      (node (ref "C22") (pin "1") (pinfunction "1_1") (pintype "passive"))
      (node (ref "D2") (pin "K") (pinfunction "K_K") (pintype "passive"))
      (node (ref "R30") (pin "1") (pinfunction "1_1") (pintype "passive"))
    )
    (net (code "33") (name "Net-(D1-B_C)") (class "Default")
      (node (ref "D1") (pin "1") (pinfunction "B_C_1") (pintype "passive"))
      (node (ref "R6") (pin "1") (pinfunction "1_1") (pintype "passive"))
    )
    (net (code "34") (name "Net-(D1-G_C)") (class "Default")
      (node (ref "D1") (pin "3") (pinfunction "G_C_3") (pintype "passive"))
      (node (ref "R4") (pin "1") (pinfunction "1_1") (pintype "passive"))
    )
    (net (code "35") (name "Net-(D1-R_C)") (class "Default")
      (node (ref "D1") (pin "2") (pinfunction "R_C_2") (pintype "passive"))
      (node (ref "R5") (pin "1") (pinfunction "1_1") (pintype "passive"))
    )
    (net (code "36") (name "Net-(D3-PadAC2)") (class "Default")
      (node (ref "D3") (pin "AC2") (pinfunction "AC2_AC2") (pintype "passive"))
      (node (ref "F2") (pin "2") (pinfunction "2_2") (pintype "passive"))
    )
    (net (code "37") (name "Net-(D4-A)") (class "Default")
      (node (ref "D4") (pin "2") (pinfunction "A_2") (pintype "passive"))
      (node (ref "T1") (pin "5") (pinfunction "5_5") (pintype "passive"))
    )
    (net (code "38") (name "Net-(D6-A)") (class "Default")
      (node (ref "D6") (pin "2") (pinfunction "A_2") (pintype "passive"))
      (node (ref "T1") (pin "9") (pinfunction "9_9") (pintype "passive"))
    )
    (net (code "39") (name "Net-(D6-K)") (class "Default")
      (node (ref "C23") (pin "1") (pinfunction "1_1") (pintype "passive"))
      (node (ref "D6") (pin "1") (pinfunction "K_1") (pintype "passive"))
    )
    (net (code "40") (name "Net-(IC1A-1IN+)") (class "Default")
      (node (ref "IC1") (pin "3") (pinfunction "1IN+_3") (pintype "passive"))
      (node (ref "R42") (pin "2") (pinfunction "2_2") (pintype "passive"))
    )
    (net (code "41") (name "Net-(IC1A-1IN-)") (class "Default")
      (node (ref "IC1") (pin "2") (pinfunction "1IN-_2") (pintype "passive"))
      (node (ref "R38") (pin "2") (pinfunction "2_2") (pintype "passive"))
      (node (ref "R39") (pin "1") (pinfunction "1_1") (pintype "passive"))
    )
    (net (code "42") (name "Net-(IC1B-2IN+)") (class "Default")
      (node (ref "D7") (pin "A") (pinfunction "A_A") (pintype "passive"))
      (node (ref "IC1") (pin "5") (pinfunction "2IN+_5") (pintype "passive"))
      (node (ref "R37") (pin "2") (pinfunction "2_2") (pintype "passive"))
      (node (ref "R46") (pin "2") (pinfunction "2_2") (pintype "passive"))
    )
    (net (code "43") (name "Net-(IC1B-2OUT)") (class "Default")
      (node (ref "D8") (pin "A") (pinfunction "A_A") (pintype "passive"))
      (node (ref "IC1") (pin "7") (pinfunction "2OUT_7") (pintype "passive"))
    )
    (net (code "44") (name "Net-(IC1C-3IN+)") (class "Default")
      (node (ref "IC1") (pin "10") (pinfunction "3IN+_10") (pintype "passive"))
      (node (ref "R47") (pin "2") (pinfunction "2_2") (pintype "passive"))
      (node (ref "R48") (pin "1") (pinfunction "1_1") (pintype "passive"))
    )
    (net (code "45") (name "Net-(IC1C-3IN-)") (class "Default")
      (node (ref "IC1") (pin "9") (pinfunction "3IN-_9") (pintype "passive"))
      (node (ref "R43") (pin "2") (pinfunction "2_2") (pintype "passive"))
      (node (ref "R44") (pin "1") (pinfunction "1_1") (pintype "passive"))
    )
    (net (code "46") (name "Net-(IC1C-3OUT)") (class "Default")
      (node (ref "IC1") (pin "8") (pinfunction "3OUT_8") (pintype "passive"))
      (node (ref "R44") (pin "2") (pinfunction "2_2") (pintype "passive"))
      (node (ref "R46") (pin "1") (pinfunction "1_1") (pintype "passive"))
    )
    (net (code "47") (name "Net-(IC1D-4IN+)") (class "Default")
      (node (ref "IC1") (pin "12") (pinfunction "4IN+_12") (pintype "passive"))
      (node (ref "R40") (pin "2") (pinfunction "2_2") (pintype "passive"))
      (node (ref "R41") (pin "1") (pinfunction "1_1") (pintype "passive"))
    )
    (net (code "48") (name "Net-(IC1D-4IN-)") (class "Default")
      (node (ref "IC1") (pin "13") (pinfunction "4IN-_13") (pintype "passive"))
      (node (ref "R35") (pin "2") (pinfunction "2_2") (pintype "passive"))
      (node (ref "R36") (pin "1") (pinfunction "1_1") (pintype "passive"))
    )
    (net (code "49") (name "Net-(IC1D-4OUT)") (class "Default")
      (node (ref "IC1") (pin "14") (pinfunction "4OUT_14") (pintype "passive"))
      (node (ref "R36") (pin "2") (pinfunction "2_2") (pintype "passive"))
      (node (ref "R37") (pin "1") (pinfunction "1_1") (pintype "passive"))
    )
    (net (code "50") (name "Net-(IC2-CF)") (class "Default")
      (node (ref "IC2") (pin "11") (pinfunction "CF_11") (pintype "passive"))
      (node (ref "R34") (pin "1") (pinfunction "1_1") (pintype "passive"))
    )
    (net (code "51") (name "Net-(IC2-CLKIN)") (class "Default")
      (node (ref "C10") (pin "1") (pinfunction "1_1") (pintype "passive"))
      (node (ref "IC2") (pin "15") (pinfunction "CLKIN_15") (pintype "passive"))
      (node (ref "X1") (pin "2") (pinfunction "2_2") (pintype "passive"))
    )
    (net (code "52") (name "Net-(IC2-CLKOUT)") (class "Default")
      (node (ref "C13") (pin "2") (pinfunction "2_2") (pintype "passive"))
      (node (ref "IC2") (pin "16") (pinfunction "CLKOUT_16") (pintype "passive"))
      (node (ref "X1") (pin "1") (pinfunction "1_1") (pintype "passive"))
    )
    (net (code "53") (name "Net-(IC2-DIN)") (class "Default")
      (node (ref "IC2") (pin "20") (pinfunction "DIN_20") (pintype "passive"))
      (node (ref "R19") (pin "1") (pinfunction "1_1") (pintype "passive"))
    )
    (net (code "54") (name "Net-(IC2-DOUT)") (class "Default")
      (node (ref "IC2") (pin "19") (pinfunction "DOUT_19") (pintype "passive"))
      (node (ref "R26") (pin "1") (pinfunction "1_1") (pintype "passive"))
    )
    (net (code "55") (name "Net-(IC2-REF-IN{slash}OUT)") (class "Default")
      (node (ref "C17") (pin "1") (pinfunction "1_1") (pintype "passive"))
      (node (ref "C18") (pin "2") (pinfunction "2_2") (pintype "passive"))
      (node (ref "IC2") (pin "9") (pinfunction "REF-IN/OUT_9") (pintype "passive"))
    )
    (net (code "56") (name "Net-(IC2-SCLK)") (class "Default")
      (node (ref "IC2") (pin "18") (pinfunction "SCLK_18") (pintype "passive"))
      (node (ref "R21") (pin "1") (pinfunction "1_1") (pintype "passive"))
    )
    (net (code "57") (name "Net-(IC2-V1N)") (class "Default")
      (node (ref "C15") (pin "2") (pinfunction "2_2") (pintype "passive"))
      (node (ref "IC2") (pin "5") (pinfunction "V1N_5") (pintype "passive"))
      (node (ref "R12") (pin "2") (pinfunction "2_2") (pintype "passive"))
    )
    (net (code "58") (name "Net-(IC2-V1P)") (class "Default")
      (node (ref "C12") (pin "2") (pinfunction "2_2") (pintype "passive"))
      (node (ref "IC2") (pin "4") (pinfunction "V1P_4") (pintype "passive"))
      (node (ref "R10") (pin "2") (pinfunction "2_2") (pintype "passive"))
    )
    (net (code "59") (name "Net-(IC2-V2N)") (class "Default")
      (node (ref "C16") (pin "2") (pinfunction "2_2") (pintype "passive"))
      (node (ref "IC2") (pin "6") (pinfunction "V2N_6") (pintype "passive"))
      (node (ref "R13") (pin "2") (pinfunction "2_2") (pintype "passive"))
    )
    (net (code "60") (name "Net-(IC2-V2P)") (class "Default")
      (node (ref "C19") (pin "2") (pinfunction "2_2") (pintype "passive"))
      (node (ref "IC2") (pin "7") (pinfunction "V2P_7") (pintype "passive"))
      (node (ref "R15") (pin "2") (pinfunction "2_2") (pintype "passive"))
      (node (ref "R17") (pin "2") (pinfunction "2_2") (pintype "passive"))
    )
    (net (code "61") (name "Net-(IC2-ZX)") (class "Default")
      (node (ref "IC2") (pin "12") (pinfunction "ZX_12") (pintype "passive"))
      (node (ref "R33") (pin "1") (pinfunction "1_1") (pintype "passive"))
    )
    (net (code "62") (name "Net-(IC2-~{CS})") (class "Default")
      (node (ref "IC2") (pin "17") (pinfunction "~{CS}_17") (pintype "passive"))
      (node (ref "R22") (pin "1") (pinfunction "1_1") (pintype "passive"))
    )
    (net (code "63") (name "Net-(IC3-BP)") (class "Default")
      (node (ref "C2") (pin "1") (pinfunction "1_1") (pintype "passive"))
      (node (ref "IC3") (pin "3") (pinfunction "BP_3") (pintype "passive"))
      (node (ref "IC5") (pin "4") (pinfunction "COL_4") (pintype "passive"))
    )
    (net (code "64") (name "Net-(IC3-D)") (class "Default")
      (node (ref "D2") (pin "A") (pinfunction "A_A") (pintype "passive"))
      (node (ref "IC3") (pin "5") (pinfunction "D_5") (pintype "passive"))
      (node (ref "T1") (pin "7") (pinfunction "7_7") (pintype "passive"))
    )
    (net (code "65") (name "Net-(IC3-FB)") (class "Default")
      (node (ref "IC3") (pin "4") (pinfunction "FB_4") (pintype "passive"))
      (node (ref "IC5") (pin "3") (pinfunction "EMIT_3") (pintype "passive"))
    )
    (net (code "66") (name "Net-(IC4-CATHODE)") (class "Default")
      (node (ref "C32") (pin "1") (pinfunction "1_1") (pintype "passive"))
      (node (ref "IC4") (pin "2") (pinfunction "CATHODE_2") (pintype "passive"))
      (node (ref "IC5") (pin "2") (pinfunction "C_2") (pintype "passive"))
    )
    (net (code "67") (name "Net-(IC4-REF)") (class "Default")
      (node (ref "C32") (pin "2") (pinfunction "2_2") (pintype "passive"))
      (node (ref "IC4") (pin "1") (pinfunction "REF_1") (pintype "passive"))
      (node (ref "R28") (pin "1") (pinfunction "1_1") (pintype "passive"))
      (node (ref "R29") (pin "2") (pinfunction "2_2") (pintype "passive"))
    )
    (net (code "68") (name "Net-(IC5-A)") (class "Default")
      (node (ref "IC5") (pin "1") (pinfunction "A_1") (pintype "passive"))
      (node (ref "R27") (pin "1") (pinfunction "1_1") (pintype "passive"))
    )
    (net (code "69") (name "Net-(IN1-IN)") (class "Default")
      (node (ref "F1") (pin "1") (pinfunction "1_1") (pintype "passive"))
      (node (ref "IN1") (pin "1") (pinfunction "IN_1") (pintype "passive"))
    )
    (net (code "70") (name "Net-(J6-1)") (class "Default")
      (node (ref "J6") (pin "01") (pinfunction "1_01") (pintype "passive"))
      (node (ref "R40") (pin "1") (pinfunction "1_1") (pintype "passive"))
      (node (ref "R43") (pin "1") (pinfunction "1_1") (pintype "passive"))
      (node (ref "R49") (pin "2") (pinfunction "2_2") (pintype "passive"))
    )
    (net (code "71") (name "Net-(J6-2)") (class "Default")
      (node (ref "J6") (pin "02") (pinfunction "2_02") (pintype "passive"))
      (node (ref "R35") (pin "1") (pinfunction "1_1") (pintype "passive"))
      (node (ref "R47") (pin "1") (pinfunction "1_1") (pintype "passive"))
      (node (ref "R49") (pin "1") (pinfunction "1_1") (pintype "passive"))
    )
    (net (code "72") (name "Net-(K1-COIL1)") (class "Default")
      (node (ref "D5") (pin "A") (pinfunction "A_A") (pintype "passive"))
      (node (ref "K1") (pin "1") (pinfunction "COIL1_1") (pintype "passive"))
      (node (ref "K2") (pin "2") (pinfunction "COIL2_2") (pintype "passive"))
      (node (ref "Q2") (pin "3") (pinfunction "C_3") (pintype "passive"))
    )
    (net (code "73") (name "Net-(M1-EN)") (class "Default")
      (node (ref "C24") (pin "2") (pinfunction "2_2") (pintype "passive"))
      (node (ref "M1") (pin "3") (pinfunction "EN_3") (pintype "passive"))
      (node (ref "R3") (pin "1") (pinfunction "1_1") (pintype "passive"))
      (node (ref "SW2") (pin "12") (pinfunction "2_12") (pintype "passive"))
    )
    (net (code "74") (name "Net-(M1-IO0)") (class "Default")
      (node (ref "C21") (pin "2") (pinfunction "2_2") (pintype "passive"))
      (node (ref "M1") (pin "25") (pinfunction "IO0_25") (pintype "passive"))
      (node (ref "R1") (pin "1") (pinfunction "1_1") (pintype "passive"))
      (node (ref "SW1") (pin "12") (pinfunction "2_12") (pintype "passive"))
    )
    (net (code "75") (name "Net-(M1-IO26)") (class "Default")
      (node (ref "C29") (pin "2") (pinfunction "2_2") (pintype "passive"))
      (node (ref "M1") (pin "11") (pinfunction "IO26_11") (pintype "passive"))
      (node (ref "SW3") (pin "1") (pinfunction "COM_1") (pintype "passive"))
    )
    (net (code "76") (name "Net-(Q2-B)") (class "Default")
      (node (ref "Q2") (pin "1") (pinfunction "B_1") (pintype "passive"))
      (node (ref "Q3") (pin "3") (pinfunction "C_3") (pintype "passive"))
      (node (ref "R55") (pin "2") (pinfunction "2_2") (pintype "passive"))
    )
    (net (code "77") (name "Net-(Q3-B)") (class "Default")
      (node (ref "Q3") (pin "1") (pinfunction "B_1") (pintype "passive"))
      (node (ref "R58") (pin "2") (pinfunction "2_2") (pintype "passive"))
    )
    (net (code "78") (name "Net-(R14-Pad1)") (class "Default")
      (node (ref "R14") (pin "1") (pinfunction "1_1") (pintype "passive"))
      (node (ref "R16") (pin "1") (pinfunction "1_1") (pintype "passive"))
    )
    (net (code "79") (name "Net-(R14-Pad2)") (class "Default")
      (node (ref "R14") (pin "2") (pinfunction "2_2") (pintype "passive"))
      (node (ref "R15") (pin "1") (pinfunction "1_1") (pintype "passive"))
    )
    (net (code "80") (name "Net-(R16-Pad2)") (class "Default")
      (node (ref "R16") (pin "2") (pinfunction "2_2") (pintype "passive"))
      (node (ref "R18") (pin "2") (pinfunction "2_2") (pintype "passive"))
    )
    (net (code "81") (name "unconnected-(IC8-OUT-Pad2)") (class "Default")
      (node (ref "IC8") (pin "2") (pinfunction "OUT_2") (pintype "passive+no_connect"))
    )
    (net (code "82") (name "unconnected-(K1-COM-Pad3)") (class "Default")
      (node (ref "K1") (pin "3") (pinfunction "COM_3") (pintype "passive+no_connect"))
    )
    (net (code "83") (name "unconnected-(K2-NO-Pad4)") (class "Default")
      (node (ref "K2") (pin "4") (pinfunction "NO_4") (pintype "passive+no_connect"))
    )
    (net (code "84") (name "unconnected-(M1-IO12-Pad14)") (class "Default")
      (node (ref "M1") (pin "14") (pinfunction "IO12_14") (pintype "passive+no_connect"))
    )
    (net (code "85") (name "unconnected-(M1-IO16-Pad27)") (class "Default")
      (node (ref "M1") (pin "27") (pinfunction "IO16_27") (pintype "passive+no_connect"))
    )
    (net (code "86") (name "unconnected-(M1-IO17-Pad28)") (class "Default")
      (node (ref "M1") (pin "28") (pinfunction "IO17_28") (pintype "passive+no_connect"))
    )
    (net (code "87") (name "unconnected-(M1-IO27-Pad12)") (class "Default")
      (node (ref "M1") (pin "12") (pinfunction "IO27_12") (pintype "passive+no_connect"))
    )
    (net (code "88") (name "unconnected-(M1-IO34-Pad6)") (class "Default")
      (node (ref "M1") (pin "6") (pinfunction "IO34_6") (pintype "passive+no_connect"))
    )
    (net (code "89") (name "unconnected-(M1-IO35-Pad7)") (class "Default")
      (node (ref "M1") (pin "7") (pinfunction "IO35_7") (pintype "passive+no_connect"))
    )
    (net (code "90") (name "unconnected-(M1-NC-Pad17)") (class "Default")
      (node (ref "M1") (pin "17") (pinfunction "NC_17") (pintype "passive+no_connect"))
    )
    (net (code "91") (name "unconnected-(M1-NC-Pad18)") (class "Default")
      (node (ref "M1") (pin "18") (pinfunction "NC_18") (pintype "passive+no_connect"))
    )
    (net (code "92") (name "unconnected-(M1-NC-Pad19)") (class "Default")
      (node (ref "M1") (pin "19") (pinfunction "NC_19") (pintype "passive+no_connect"))
    )
    (net (code "93") (name "unconnected-(M1-NC-Pad20)") (class "Default")
      (node (ref "M1") (pin "20") (pinfunction "NC_20") (pintype "passive+no_connect"))
    )
    (net (code "94") (name "unconnected-(M1-NC-Pad21)") (class "Default")
      (node (ref "M1") (pin "21") (pinfunction "NC_21") (pintype "passive+no_connect"))
    )
    (net (code "95") (name "unconnected-(M1-NC-Pad22)") (class "Default")
      (node (ref "M1") (pin "22") (pinfunction "NC_22") (pintype "passive+no_connect"))
    )
    (net (code "96") (name "unconnected-(M1-NC-Pad32)") (class "Default")
      (node (ref "M1") (pin "32") (pinfunction "NC_32") (pintype "passive+no_connect"))
    )
    (net (code "97") (name "unconnected-(M1-VN-Pad5)") (class "Default")
      (node (ref "M1") (pin "5") (pinfunction "VN_5") (pintype "passive+no_connect"))
    )
    (net (code "98") (name "unconnected-(M1-VP-Pad4)") (class "Default")
      (node (ref "M1") (pin "4") (pinfunction "VP_4") (pintype "passive+no_connect"))
    )
    (net (code "99") (name "unconnected-(SW1-1-Pad21)") (class "Default")
      (node (ref "SW1") (pin "21") (pinfunction "1_21") (pintype "passive+no_connect"))
    )
    (net (code "100") (name "unconnected-(SW1-2-Pad22)") (class "Default")
      (node (ref "SW1") (pin "22") (pinfunction "2_22") (pintype "passive+no_connect"))
    )
    (net (code "101") (name "unconnected-(SW2-1-Pad21)") (class "Default")
      (node (ref "SW2") (pin "21") (pinfunction "1_21") (pintype "passive+no_connect"))
    )
    (net (code "102") (name "unconnected-(SW2-2-Pad22)") (class "Default")
      (node (ref "SW2") (pin "22") (pinfunction "2_22") (pintype "passive+no_connect"))
    )
    (net (code "103") (name "unconnected-(T1-Pad2)") (class "Default")
      (node (ref "T1") (pin "2") (pinfunction "2_2") (pintype "passive+no_connect"))
    )
    (net (code "104") (name "unconnected-(T1-Pad3)") (class "Default")
      (node (ref "T1") (pin "3") (pinfunction "3_3") (pintype "passive+no_connect"))
    )
    (net (code "105") (name "unconnected-(T1-Pad4)") (class "Default")
      (node (ref "T1") (pin "4") (pinfunction "4_4") (pintype "passive+no_connect"))
    )
    (net (code "106") (name "unconnected-(T1-Pad8)") (class "Default")
      (node (ref "T1") (pin "8") (pinfunction "8_8") (pintype "passive+no_connect"))
    )
  )
)
